# rekick2015-001.net
KiCad netlist of a schematic drawn in EAGLE
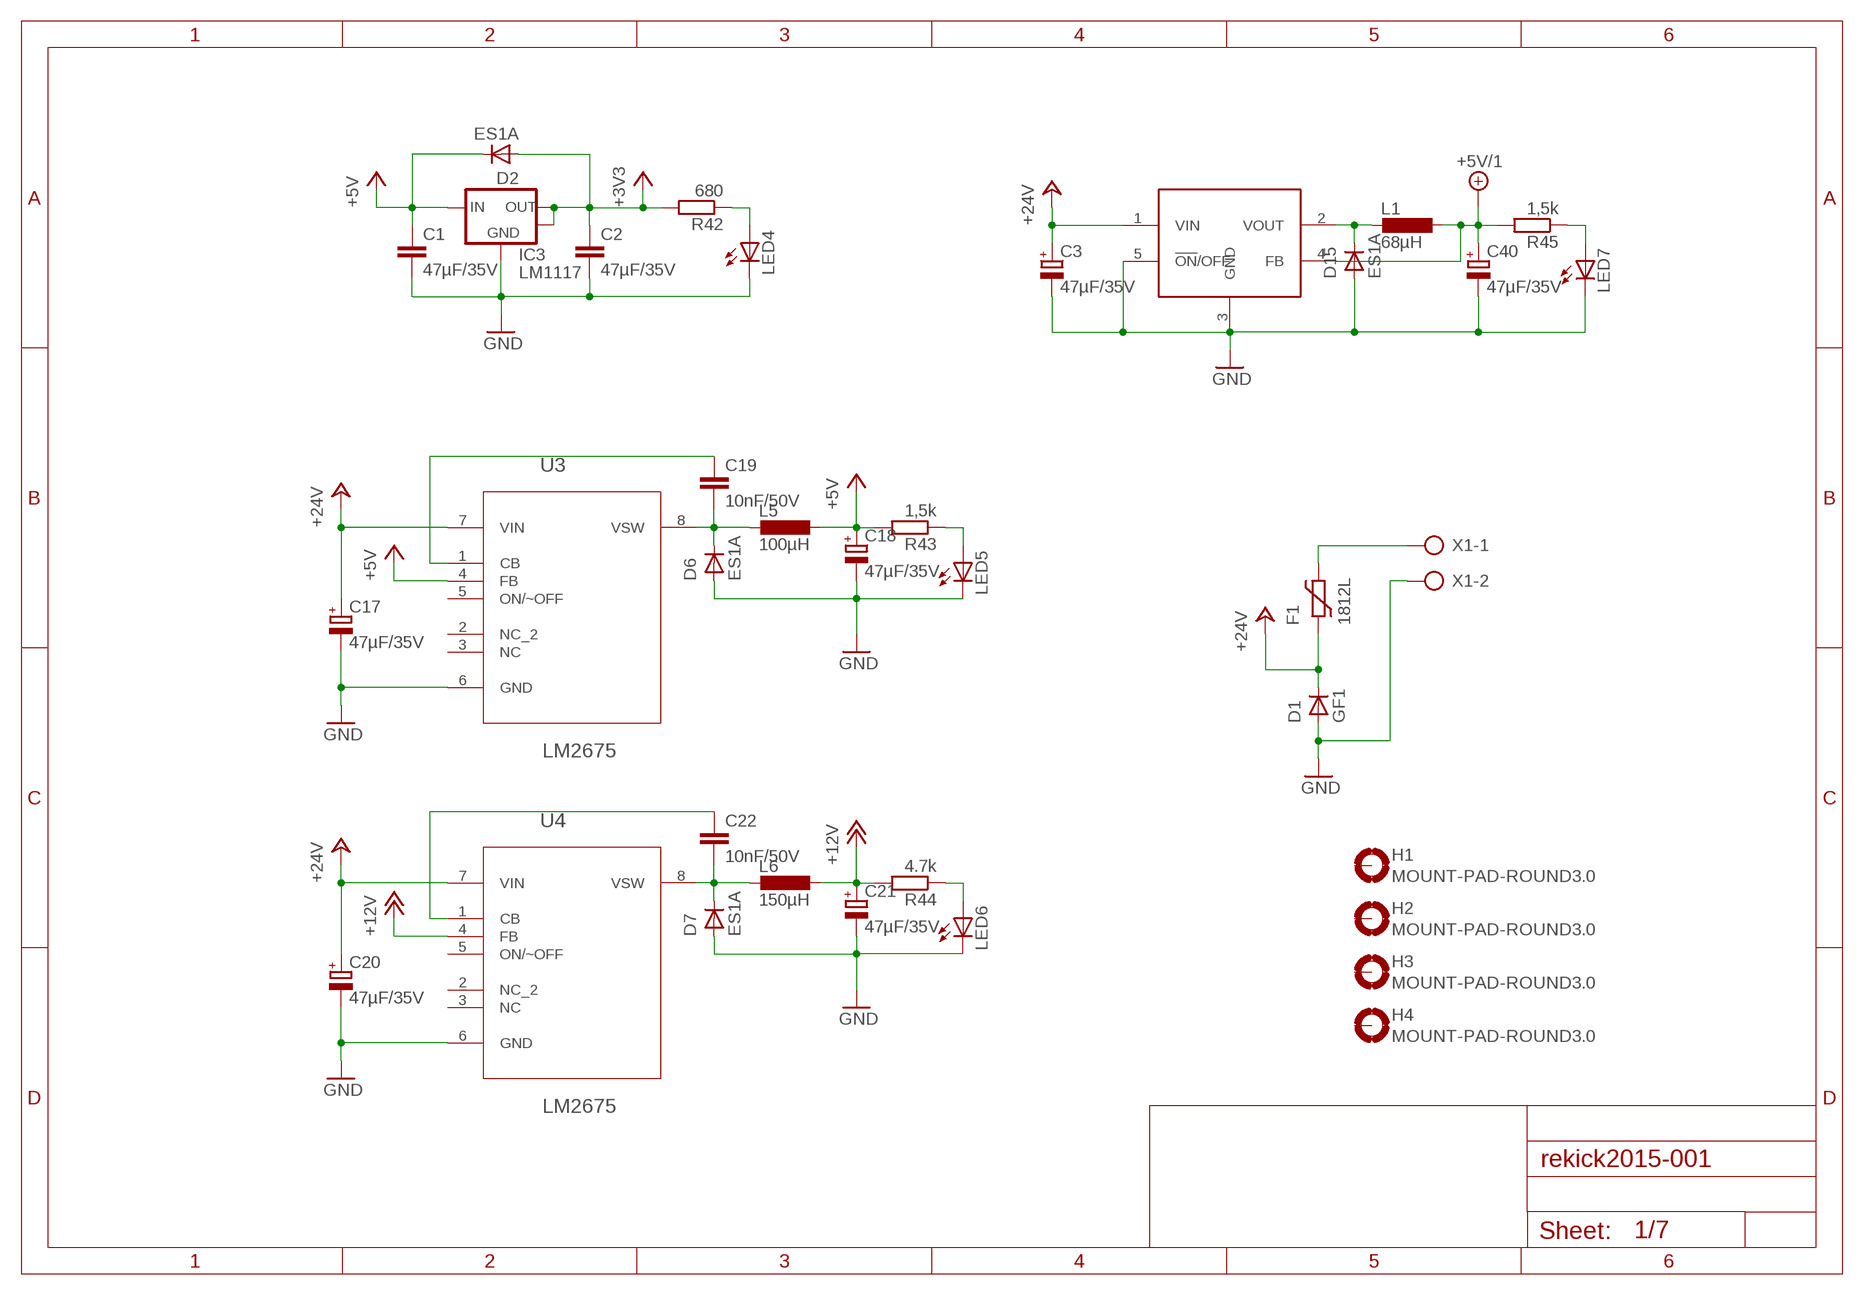
[diagram p0: schematic, sheet 1]
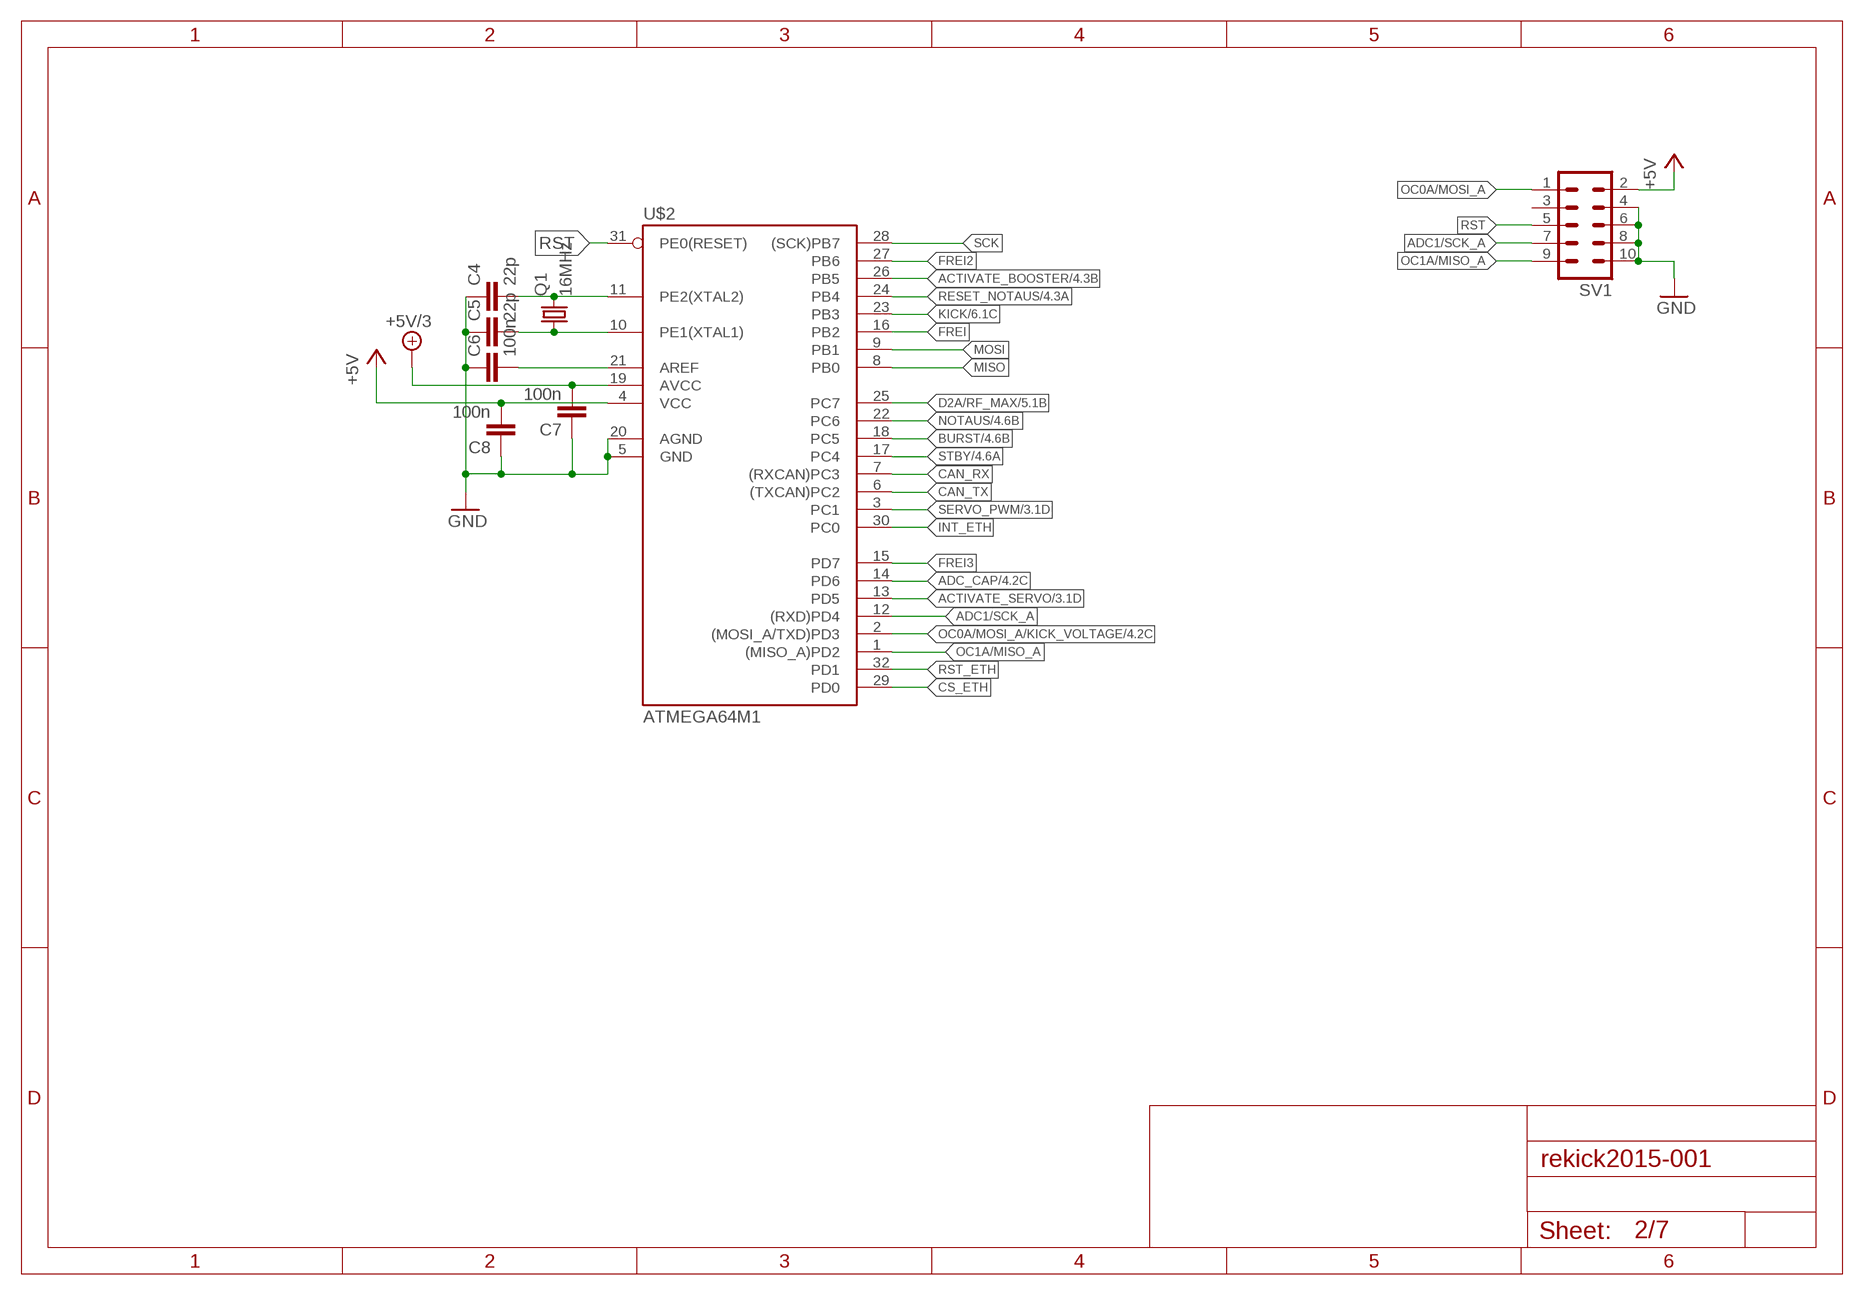
[diagram p1: schematic, sheet 2]
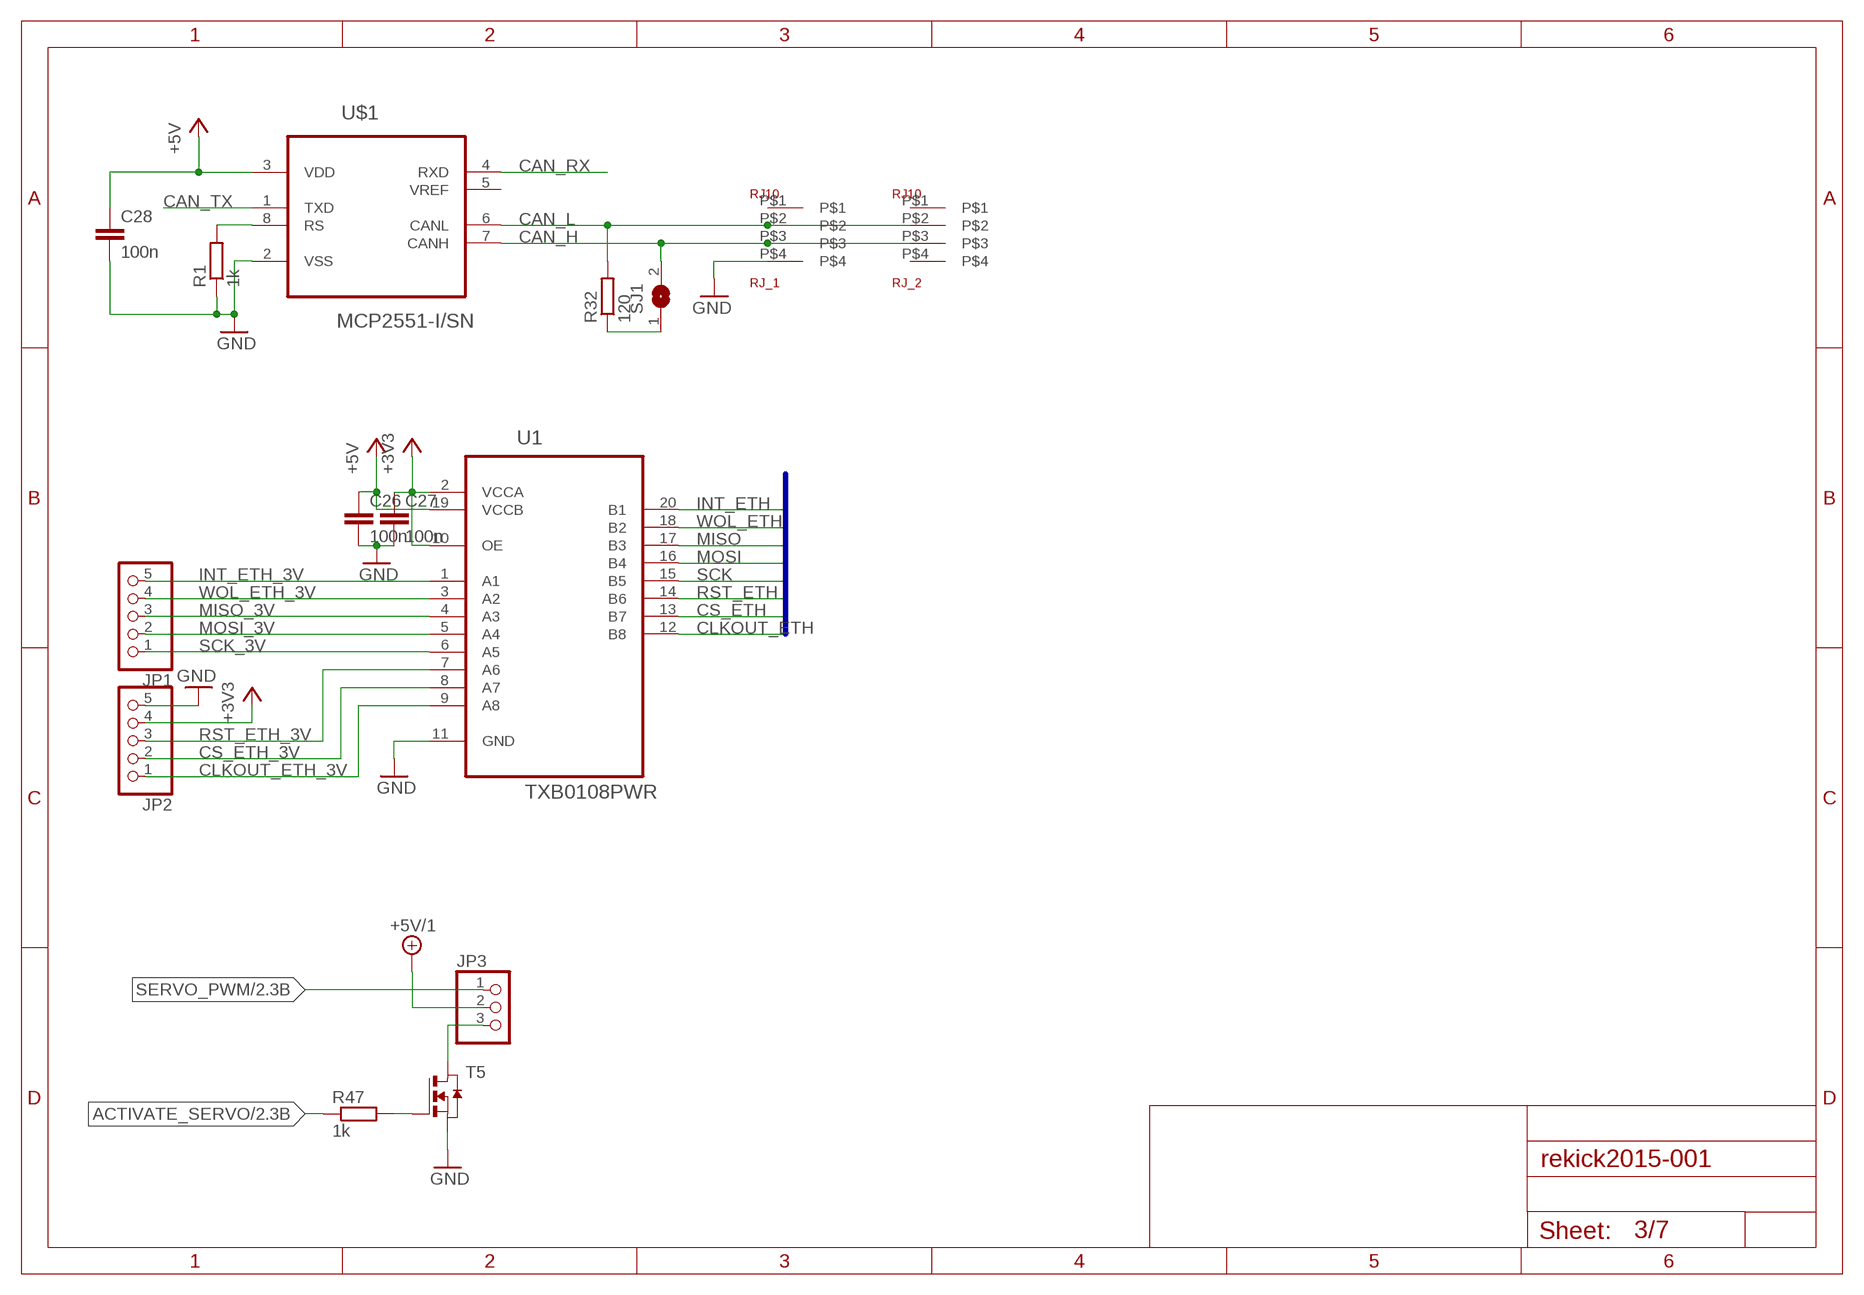
[diagram p2: schematic, sheet 3]
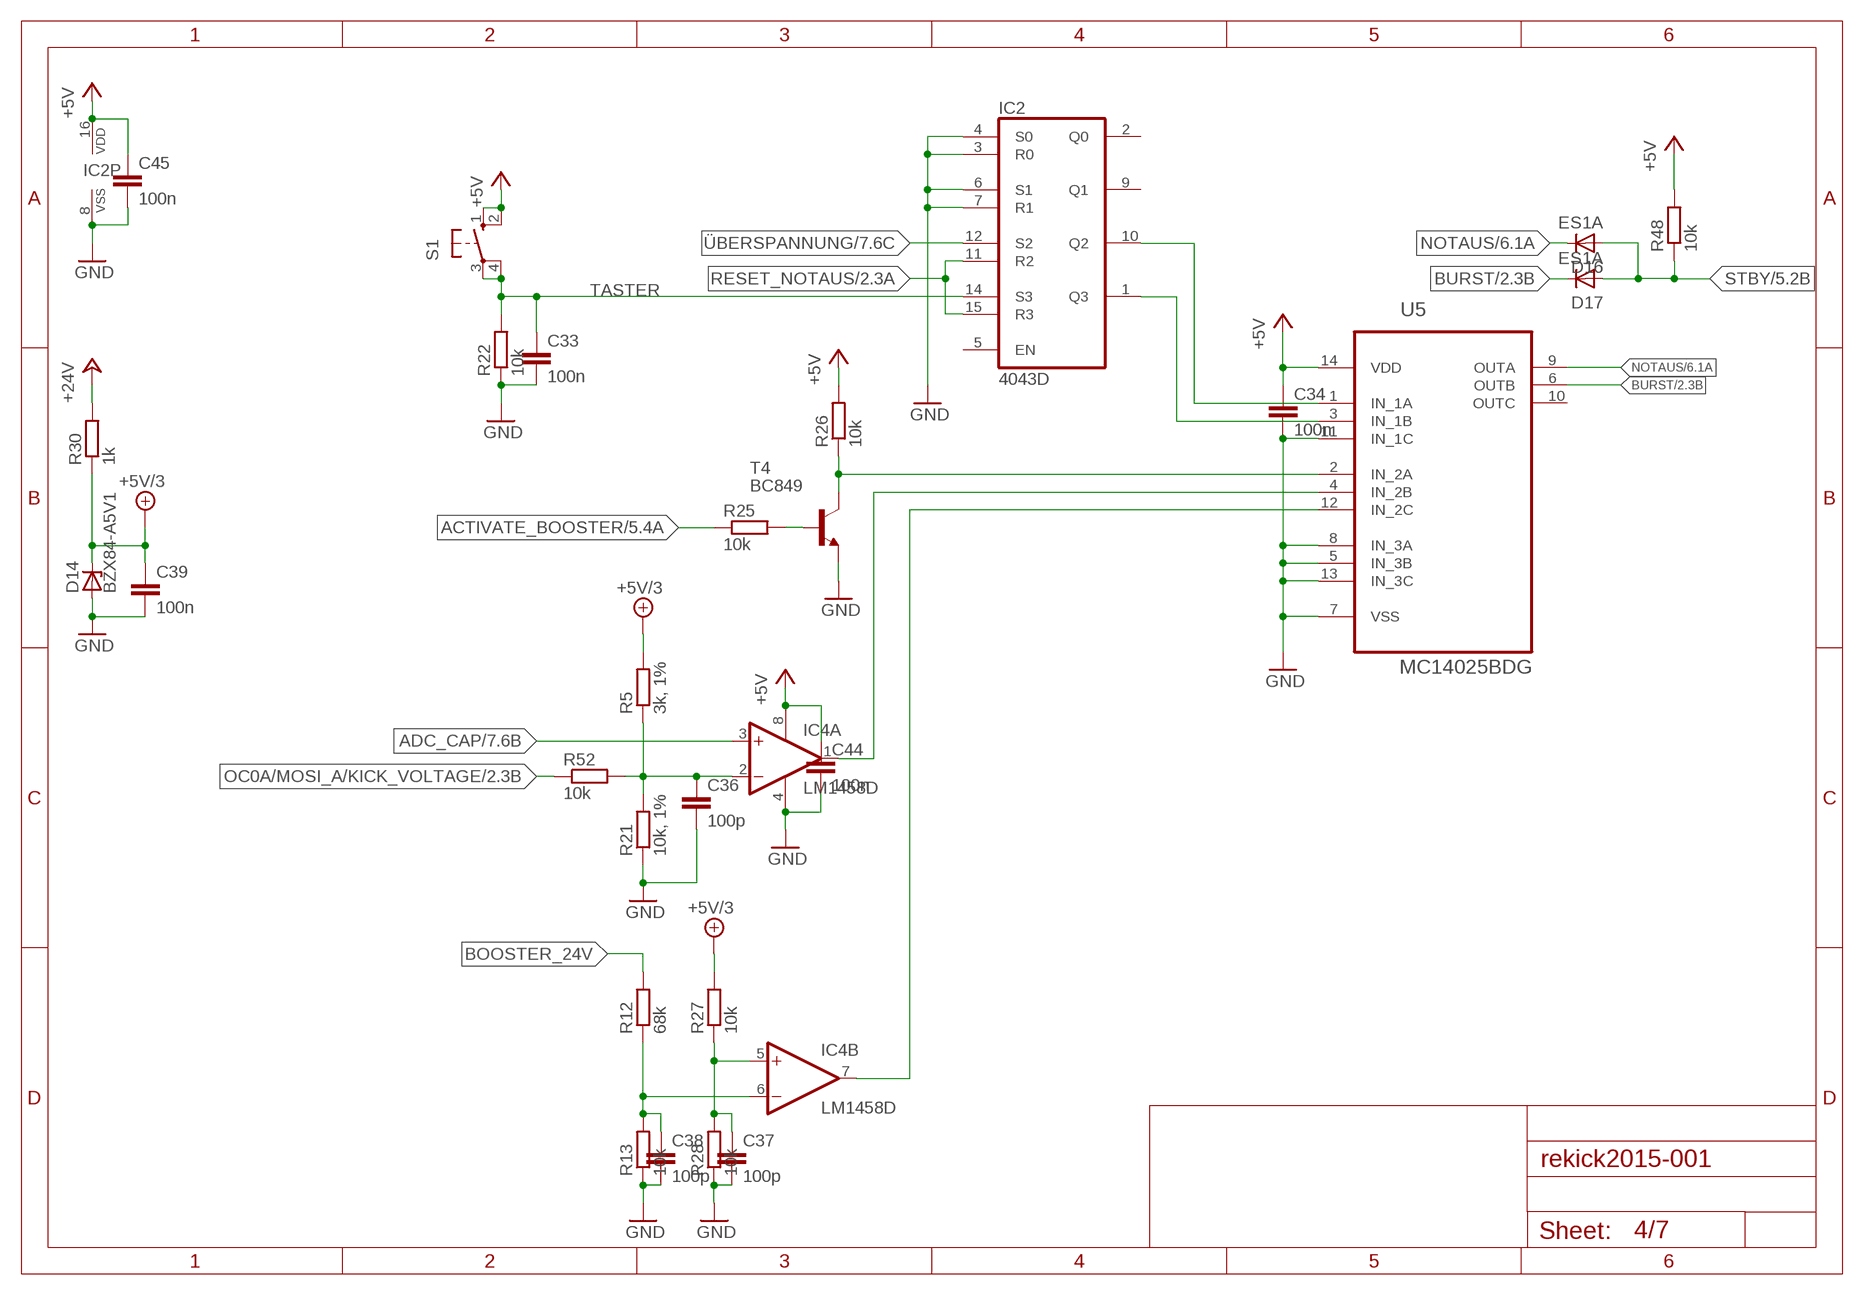
[diagram p3: schematic, sheet 4]
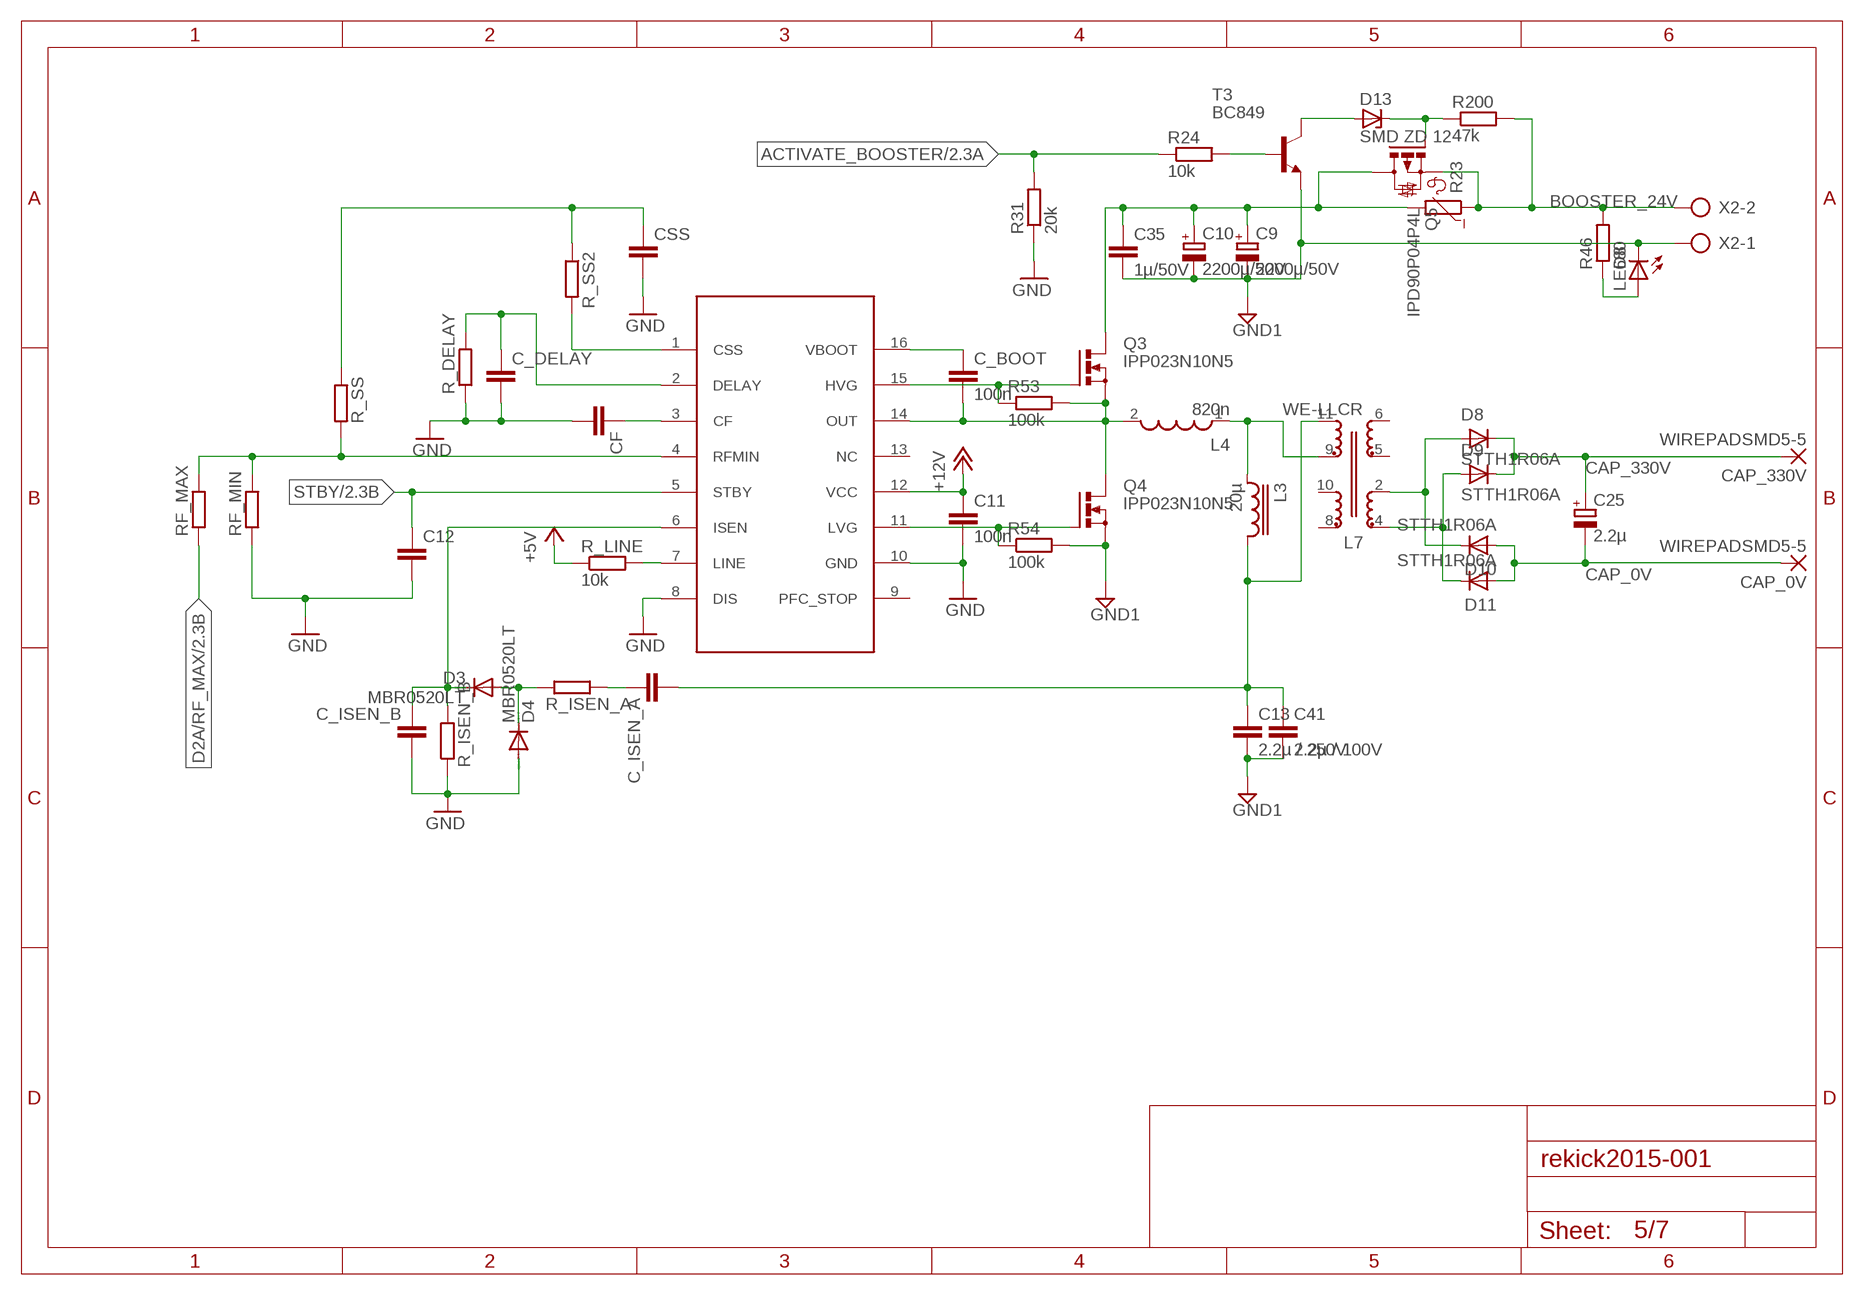
[diagram p4: schematic, sheet 5]
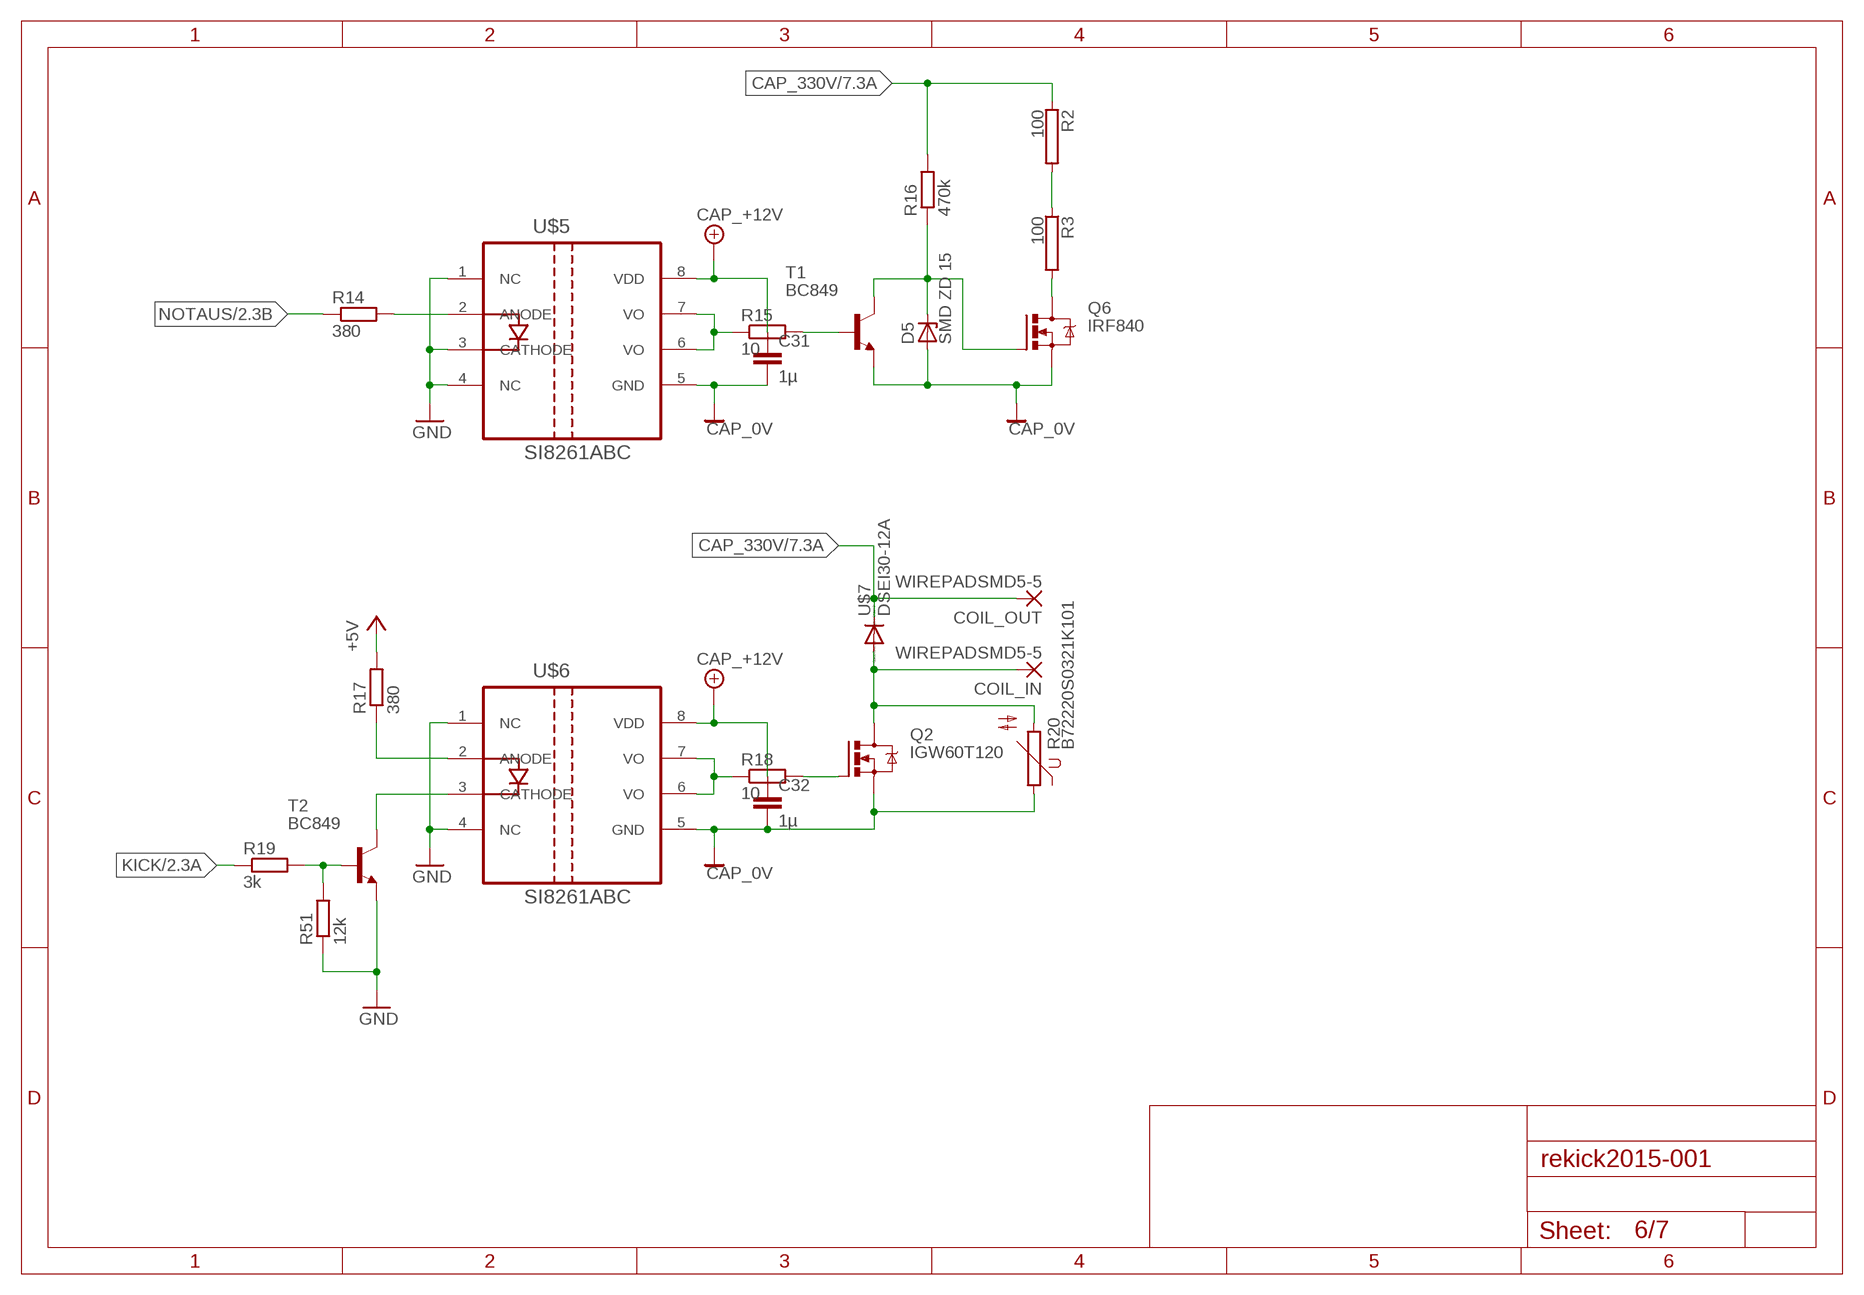
[diagram p5: schematic, sheet 6]
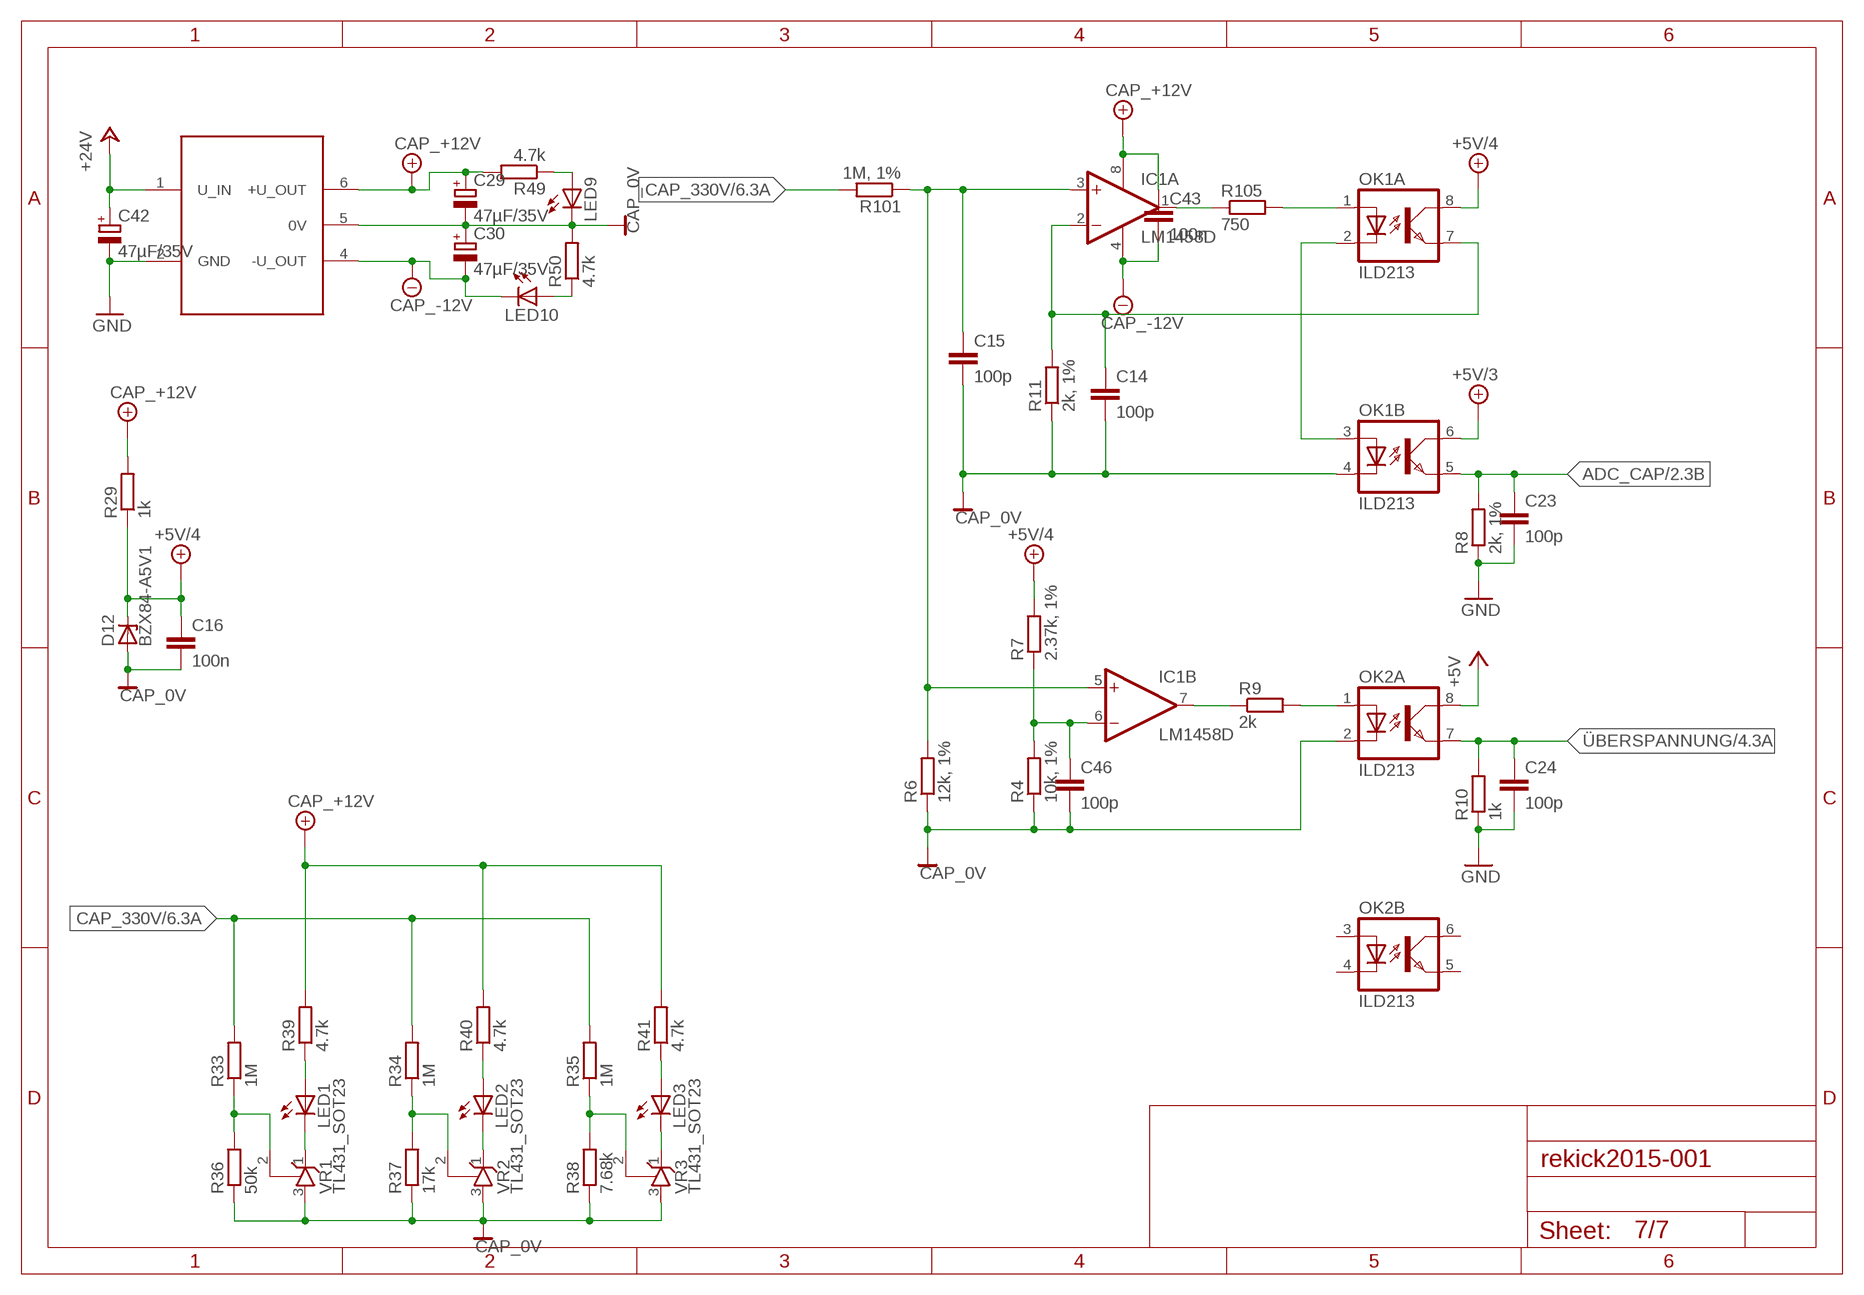
[diagram p6: schematic, sheet 7]

(export (version "E")
  (design (tool "Eeschema 10.0.6"))
  (components
    (comp (ref "C9")
      (value "2200µ/50V")
      (footprint "eagle-import:E5-13")
      (libsource (lib "eagle-import") (part "CPOL-EUE5-13"))
    )
    (comp (ref "C10")
      (value "2200µ/50V")
      (footprint "eagle-import:E5-13")
      (libsource (lib "eagle-import") (part "CPOL-EUE5-13"))
    )
    (comp (ref "C11")
      (value "100n")
      (footprint "eagle-import:C0603")
      (libsource (lib "eagle-import") (part "C-EUC0603"))
    )
    (comp (ref "C12")
      (value "C-EUC0603")
      (footprint "eagle-import:C0603")
      (libsource (lib "eagle-import") (part "C-EUC0603"))
    )
    (comp (ref "C13")
      (value "2.2µ / 250V")
      (footprint "eagle-import:C2220K")
      (libsource (lib "eagle-import") (part "C-EUC2220K"))
    )
    (comp (ref "C25")
      (value "2.2µ")
      (footprint "eagle-import:E5-10,5")
      (libsource (lib "eagle-import") (part "CPOL-EUE5-10.5"))
    )
    (comp (ref "C35")
      (value "1µ/50V")
      (footprint "eagle-import:C0603")
      (libsource (lib "eagle-import") (part "C-EUC0603"))
    )
    (comp (ref "C41")
      (value "2.2µ / 100V")
      (footprint "eagle-import:C1210K")
      (libsource (lib "eagle-import") (part "C-EUC1210K"))
    )
    (comp (ref "CAP_0V")
      (value "WIREPADSMD5-5")
      (footprint "eagle-import:5-5")
      (libsource (lib "eagle-import") (part "WIREPADSMD5-5"))
    )
    (comp (ref "CAP_330V")
      (value "WIREPADSMD5-5")
      (footprint "eagle-import:5-5")
      (libsource (lib "eagle-import") (part "WIREPADSMD5-5"))
    )
    (comp (ref "CF")
      (value "C-EUC0603")
      (footprint "eagle-import:C0603")
      (libsource (lib "eagle-import") (part "C-EUC0603"))
    )
    (comp (ref "CSS")
      (value "C-EUC0603")
      (footprint "eagle-import:C0603")
      (libsource (lib "eagle-import") (part "C-EUC0603"))
    )
    (comp (ref "C_BOOT")
      (value "100n")
      (footprint "eagle-import:C0603")
      (libsource (lib "eagle-import") (part "C-EUC0603"))
    )
    (comp (ref "C_DELAY")
      (value "C-EUC0603")
      (footprint "eagle-import:C0603")
      (libsource (lib "eagle-import") (part "C-EUC0603"))
    )
    (comp (ref "C_ISEN_A")
      (value "C-EUC0603")
      (footprint "eagle-import:C0603")
      (libsource (lib "eagle-import") (part "C-EUC0603"))
    )
    (comp (ref "C_ISEN_B")
      (value "C-EUC0603")
      (footprint "eagle-import:C0603")
      (libsource (lib "eagle-import") (part "C-EUC0603"))
    )
    (comp (ref "D3")
      (value "MBR0520LT")
      (footprint "eagle-import:SOD123")
      (libsource (lib "eagle-import") (part "MBR0520LT"))
    )
    (comp (ref "D4")
      (value "MBR0520LT")
      (footprint "eagle-import:SOD123")
      (libsource (lib "eagle-import") (part "MBR0520LT"))
    )
    (comp (ref "D8")
      (value "STTH1R06A")
      (footprint "eagle-import:SMA-DO214AC")
      (libsource (lib "eagle-import") (part "GF1"))
    )
    (comp (ref "D9")
      (value "STTH1R06A")
      (footprint "eagle-import:SMA-DO214AC")
      (libsource (lib "eagle-import") (part "GF1"))
    )
    (comp (ref "D10")
      (value "STTH1R06A")
      (footprint "eagle-import:SMA-DO214AC")
      (libsource (lib "eagle-import") (part "GF1"))
    )
    (comp (ref "D11")
      (value "STTH1R06A")
      (footprint "eagle-import:SMA-DO214AC")
      (libsource (lib "eagle-import") (part "GF1"))
    )
    (comp (ref "D13")
      (value "SMD ZD 12")
      (footprint "eagle-import:TO236")
      (libsource (lib "eagle-import") (part "BZX84CSMD"))
    )
    (comp (ref "L3")
      (value "20µ")
      (footprint "eagle-import:SRR1210")
      (libsource (lib "eagle-import") (part "SRR1210"))
    )
    (comp (ref "L4")
      (value "820n")
      (footprint "eagle-import:WE-HCI_1890")
      (libsource (lib "eagle-import") (part "WE-HCI_1890"))
    )
    (comp (ref "L7")
      (value "WE-LLCR")
      (footprint "eagle-import:WE-LLCR_ETD34")
      (libsource (lib "eagle-import") (part "WE-LLCR_ETD34"))
    )
    (comp (ref "LED8")
      (value "LEDCHIP-LED0805")
      (footprint "eagle-import:CHIP-LED0805")
      (libsource (lib "eagle-import") (part "LEDCHIP-LED0805"))
    )
    (comp (ref "Q3")
      (value "IPP023N10N5")
      (footprint "eagle-import:TO220BV")
      (libsource (lib "eagle-import") (part "PMOSFET_NTO220BV"))
    )
    (comp (ref "Q4")
      (value "IPP023N10N5")
      (footprint "eagle-import:TO220BV")
      (libsource (lib "eagle-import") (part "PMOSFET_NTO220BV"))
    )
    (comp (ref "Q5")
      (value "IPD90P04P4L")
      (footprint "eagle-import:D-PAK_TO252AA")
      (libsource (lib "eagle-import") (part "IRF?5305R"))
    )
    (comp (ref "R23")
      (value "NTC644A")
      (footprint "eagle-import:N644A")
      (libsource (lib "eagle-import") (part "NTC644A"))
    )
    (comp (ref "R24")
      (value "10k")
      (footprint "eagle-import:R0805")
      (libsource (lib "eagle-import") (part "R-EU_R0805"))
    )
    (comp (ref "R31")
      (value "20k")
      (footprint "eagle-import:R0805")
      (libsource (lib "eagle-import") (part "R-EU_R0805"))
    )
    (comp (ref "R46")
      (value "680")
      (footprint "eagle-import:R0805")
      (libsource (lib "eagle-import") (part "R-EU_R0805"))
    )
    (comp (ref "R53")
      (value "100k")
      (footprint "eagle-import:R0805")
      (libsource (lib "eagle-import") (part "R-EU_R0805"))
    )
    (comp (ref "R54")
      (value "100k")
      (footprint "eagle-import:R0805")
      (libsource (lib "eagle-import") (part "R-EU_R0805"))
    )
    (comp (ref "R200")
      (value "47k")
      (footprint "eagle-import:R0805")
      (libsource (lib "eagle-import") (part "R-EU_R0805"))
    )
    (comp (ref "RF_MAX")
      (value "R-EU_R0805")
      (footprint "eagle-import:R0805")
      (libsource (lib "eagle-import") (part "R-EU_R0805"))
    )
    (comp (ref "RF_MIN")
      (value "R-EU_R0805")
      (footprint "eagle-import:R0805")
      (libsource (lib "eagle-import") (part "R-EU_R0805"))
    )
    (comp (ref "R_DELAY")
      (value "R-EU_R0805")
      (footprint "eagle-import:R0805")
      (libsource (lib "eagle-import") (part "R-EU_R0805"))
    )
    (comp (ref "R_ISEN_A")
      (value "R-EU_R0805")
      (footprint "eagle-import:R0805")
      (libsource (lib "eagle-import") (part "R-EU_R0805"))
    )
    (comp (ref "R_ISEN_B")
      (value "R-EU_R0805")
      (footprint "eagle-import:R0805")
      (libsource (lib "eagle-import") (part "R-EU_R0805"))
    )
    (comp (ref "R_LINE")
      (value "10k")
      (footprint "eagle-import:R0805")
      (libsource (lib "eagle-import") (part "R-EU_R0805"))
    )
    (comp (ref "R_SS")
      (value "R-EU_R0805")
      (footprint "eagle-import:R0805")
      (libsource (lib "eagle-import") (part "R-EU_R0805"))
    )
    (comp (ref "R_SS2")
      (value "R-EU_R0805")
      (footprint "eagle-import:R0805")
      (libsource (lib "eagle-import") (part "R-EU_R0805"))
    )
    (comp (ref "T3")
      (value "BC849")
      (footprint "eagle-import:SOT23")
      (libsource (lib "eagle-import") (part "BC849"))
    )
    (comp (ref "U$3")
      (value "L6599")
      (footprint "eagle-import:SO16")
      (libsource (lib "eagle-import") (part "L6599"))
    )
    (comp (ref "X2")
      (value "AK500/2-H")
      (footprint "eagle-import:AK500_2-H")
      (libsource (lib "eagle-import") (part "AK500/2-H"))
    )
    (comp (ref "C14")
      (value "100p")
      (footprint "eagle-import:C0603")
      (libsource (lib "eagle-import") (part "C-EUC0603"))
    )
    (comp (ref "C15")
      (value "100p")
      (footprint "eagle-import:C0603")
      (libsource (lib "eagle-import") (part "C-EUC0603"))
    )
    (comp (ref "C16")
      (value "100n")
      (footprint "eagle-import:C0603")
      (libsource (lib "eagle-import") (part "C-EUC0603"))
    )
    (comp (ref "C23")
      (value "100p")
      (footprint "eagle-import:C0603")
      (libsource (lib "eagle-import") (part "C-EUC0603"))
    )
    (comp (ref "C24")
      (value "100p")
      (footprint "eagle-import:C0603")
      (libsource (lib "eagle-import") (part "C-EUC0603"))
    )
    (comp (ref "C29")
      (value "47µF/35V")
      (footprint "eagle-import:PANASONIC_D")
      (libsource (lib "eagle-import") (part "CPOL-EUD"))
    )
    (comp (ref "C30")
      (value "47µF/35V")
      (footprint "eagle-import:PANASONIC_D")
      (libsource (lib "eagle-import") (part "CPOL-EUD"))
    )
    (comp (ref "C42")
      (value "47µF/35V")
      (footprint "eagle-import:PANASONIC_D")
      (libsource (lib "eagle-import") (part "CPOL-EUD"))
    )
    (comp (ref "C43")
      (value "100n")
      (footprint "eagle-import:C0603")
      (libsource (lib "eagle-import") (part "C-EUC0603"))
    )
    (comp (ref "C46")
      (value "100p")
      (footprint "eagle-import:C0603")
      (libsource (lib "eagle-import") (part "C-EUC0603"))
    )
    (comp (ref "D12")
      (value "BZX84-A5V1")
      (footprint "eagle-import:TO236")
      (libsource (lib "eagle-import") (part "BZX84CSMD"))
    )
    (comp (ref "IC1")
      (value "LM1458D")
      (footprint "eagle-import:SO08")
      (libsource (lib "eagle-import") (part "1458DLM"))
    )
    (comp (ref "LED1")
      (value "LEDCHIP-LED0805")
      (footprint "eagle-import:CHIP-LED0805")
      (libsource (lib "eagle-import") (part "LEDCHIP-LED0805"))
    )
    (comp (ref "LED2")
      (value "LEDCHIP-LED0805")
      (footprint "eagle-import:CHIP-LED0805")
      (libsource (lib "eagle-import") (part "LEDCHIP-LED0805"))
    )
    (comp (ref "LED3")
      (value "LEDCHIP-LED0805")
      (footprint "eagle-import:CHIP-LED0805")
      (libsource (lib "eagle-import") (part "LEDCHIP-LED0805"))
    )
    (comp (ref "LED9")
      (value "LEDCHIP-LED0805")
      (footprint "eagle-import:CHIP-LED0805")
      (libsource (lib "eagle-import") (part "LEDCHIP-LED0805"))
    )
    (comp (ref "LED10")
      (value "LEDCHIP-LED0805")
      (footprint "eagle-import:CHIP-LED0805")
      (libsource (lib "eagle-import") (part "LEDCHIP-LED0805"))
    )
    (comp (ref "OK1")
      (value "ILD213")
      (footprint "eagle-import:SOIC08")
      (libsource (lib "eagle-import") (part "ILD213"))
    )
    (comp (ref "OK2")
      (value "ILD213")
      (footprint "eagle-import:SOIC08")
      (libsource (lib "eagle-import") (part "ILD213"))
    )
    (comp (ref "R4")
      (value "10k, 1%")
      (footprint "eagle-import:R0805")
      (libsource (lib "eagle-import") (part "R-EU_R0805"))
    )
    (comp (ref "R6")
      (value "12k, 1%")
      (footprint "eagle-import:R0805")
      (libsource (lib "eagle-import") (part "R-EU_R0805"))
    )
    (comp (ref "R7")
      (value "2.37k, 1%")
      (footprint "eagle-import:R0805")
      (libsource (lib "eagle-import") (part "R-EU_R0805"))
    )
    (comp (ref "R8")
      (value "2k, 1%")
      (footprint "eagle-import:R0805")
      (libsource (lib "eagle-import") (part "R-EU_R0805"))
    )
    (comp (ref "R9")
      (value "2k")
      (footprint "eagle-import:R0805")
      (libsource (lib "eagle-import") (part "R-EU_R0805"))
    )
    (comp (ref "R10")
      (value "1k")
      (footprint "eagle-import:R0805")
      (libsource (lib "eagle-import") (part "R-EU_R0805"))
    )
    (comp (ref "R11")
      (value "2k, 1%")
      (footprint "eagle-import:R0805")
      (libsource (lib "eagle-import") (part "R-EU_R0805"))
    )
    (comp (ref "R29")
      (value "1k")
      (footprint "eagle-import:R0805")
      (libsource (lib "eagle-import") (part "R-EU_R0805"))
    )
    (comp (ref "R33")
      (value "1M")
      (footprint "eagle-import:R2512")
      (libsource (lib "eagle-import") (part "R-EU_R2512"))
    )
    (comp (ref "R34")
      (value "1M")
      (footprint "eagle-import:R2512")
      (libsource (lib "eagle-import") (part "R-EU_R2512"))
    )
    (comp (ref "R35")
      (value "1M")
      (footprint "eagle-import:R2512")
      (libsource (lib "eagle-import") (part "R-EU_R2512"))
    )
    (comp (ref "R36")
      (value "50k")
      (footprint "eagle-import:R0805")
      (libsource (lib "eagle-import") (part "R-EU_R0805"))
    )
    (comp (ref "R37")
      (value "17k")
      (footprint "eagle-import:R0805")
      (libsource (lib "eagle-import") (part "R-EU_R0805"))
    )
    (comp (ref "R38")
      (value "7.68k")
      (footprint "eagle-import:R0805")
      (libsource (lib "eagle-import") (part "R-EU_R0805"))
    )
    (comp (ref "R39")
      (value "4.7k")
      (footprint "eagle-import:R0805")
      (libsource (lib "eagle-import") (part "R-EU_R0805"))
    )
    (comp (ref "R40")
      (value "4.7k")
      (footprint "eagle-import:R0805")
      (libsource (lib "eagle-import") (part "R-EU_R0805"))
    )
    (comp (ref "R41")
      (value "4.7k")
      (footprint "eagle-import:R0805")
      (libsource (lib "eagle-import") (part "R-EU_R0805"))
    )
    (comp (ref "R49")
      (value "4.7k")
      (footprint "eagle-import:R0805")
      (libsource (lib "eagle-import") (part "R-EU_R0805"))
    )
    (comp (ref "R50")
      (value "4.7k")
      (footprint "eagle-import:R0805")
      (libsource (lib "eagle-import") (part "R-EU_R0805"))
    )
    (comp (ref "R101")
      (value "1M, 1%")
      (footprint "eagle-import:R2512")
      (libsource (lib "eagle-import") (part "R-EU_R2512"))
    )
    (comp (ref "R105")
      (value "750")
      (footprint "eagle-import:R0805")
      (libsource (lib "eagle-import") (part "R-EU_R0805"))
    )
    (comp (ref "U$4")
      (value "TMH-D")
      (footprint "eagle-import:TMH-D")
      (libsource (lib "eagle-import") (part "TMH-D"))
    )
    (comp (ref "VR1")
      (value "TL431_SOT23")
      (footprint "eagle-import:SOT23")
      (libsource (lib "eagle-import") (part "TL431_SOT23"))
    )
    (comp (ref "VR2")
      (value "TL431_SOT23")
      (footprint "eagle-import:SOT23")
      (libsource (lib "eagle-import") (part "TL431_SOT23"))
    )
    (comp (ref "VR3")
      (value "TL431_SOT23")
      (footprint "eagle-import:SOT23")
      (libsource (lib "eagle-import") (part "TL431_SOT23"))
    )
    (comp (ref "C1")
      (value "47µF/35V")
      (footprint "eagle-import:C0603")
      (libsource (lib "eagle-import") (part "C-EUC0603"))
    )
    (comp (ref "C2")
      (value "47µF/35V")
      (footprint "eagle-import:C0603")
      (libsource (lib "eagle-import") (part "C-EUC0603"))
    )
    (comp (ref "C3")
      (value "47µF/35V")
      (footprint "eagle-import:PANASONIC_D")
      (libsource (lib "eagle-import") (part "CPOL-EUD"))
    )
    (comp (ref "C17")
      (value "47µF/35V")
      (footprint "eagle-import:PANASONIC_D")
      (libsource (lib "eagle-import") (part "CPOL-EUD"))
    )
    (comp (ref "C18")
      (value "47µF/35V")
      (footprint "eagle-import:PANASONIC_D")
      (libsource (lib "eagle-import") (part "CPOL-EUD"))
    )
    (comp (ref "C19")
      (value "10nF/50V")
      (footprint "eagle-import:C0603")
      (libsource (lib "eagle-import") (part "C-EUC0603"))
    )
    (comp (ref "C20")
      (value "47µF/35V")
      (footprint "eagle-import:PANASONIC_D")
      (libsource (lib "eagle-import") (part "CPOL-EUD"))
    )
    (comp (ref "C21")
      (value "47µF/35V")
      (footprint "eagle-import:PANASONIC_D")
      (libsource (lib "eagle-import") (part "CPOL-EUD"))
    )
    (comp (ref "C22")
      (value "10nF/50V")
      (footprint "eagle-import:C0603")
      (libsource (lib "eagle-import") (part "C-EUC0603"))
    )
    (comp (ref "C40")
      (value "47µF/35V")
      (footprint "eagle-import:PANASONIC_D")
      (libsource (lib "eagle-import") (part "CPOL-EUD"))
    )
    (comp (ref "D1")
      (value "GF1")
      (footprint "eagle-import:SMA-DO214AC")
      (libsource (lib "eagle-import") (part "GF1"))
    )
    (comp (ref "D2")
      (value "ES1A")
      (footprint "eagle-import:SMA-DO214AC")
      (libsource (lib "eagle-import") (part "GF1"))
    )
    (comp (ref "D6")
      (value "ES1A")
      (footprint "eagle-import:SMA-DO214AC")
      (libsource (lib "eagle-import") (part "GF1"))
    )
    (comp (ref "D7")
      (value "ES1A")
      (footprint "eagle-import:SMA-DO214AC")
      (libsource (lib "eagle-import") (part "GF1"))
    )
    (comp (ref "D15")
      (value "ES1A")
      (footprint "eagle-import:SMA-DO214AC")
      (libsource (lib "eagle-import") (part "GF1"))
    )
    (comp (ref "F1")
      (value "1812L")
      (footprint "eagle-import:1812L")
      (libsource (lib "eagle-import") (part "1812L"))
    )
    (comp (ref "H1")
      (value "MOUNT-PAD-ROUND3.0")
      (footprint "eagle-import:3,0-PAD")
      (libsource (lib "eagle-import") (part "MOUNT-PAD-ROUND3.0"))
    )
    (comp (ref "H2")
      (value "MOUNT-PAD-ROUND3.0")
      (footprint "eagle-import:3,0-PAD")
      (libsource (lib "eagle-import") (part "MOUNT-PAD-ROUND3.0"))
    )
    (comp (ref "H3")
      (value "MOUNT-PAD-ROUND3.0")
      (footprint "eagle-import:3,0-PAD")
      (libsource (lib "eagle-import") (part "MOUNT-PAD-ROUND3.0"))
    )
    (comp (ref "H4")
      (value "MOUNT-PAD-ROUND3.0")
      (footprint "eagle-import:3,0-PAD")
      (libsource (lib "eagle-import") (part "MOUNT-PAD-ROUND3.0"))
    )
    (comp (ref "IC3")
      (value "LM1117")
      (footprint "eagle-import:SOT223")
      (libsource (lib "eagle-import") (part "LM1117"))
    )
    (comp (ref "L1")
      (value "68µH")
      (footprint "eagle-import:PISM")
      (libsource (lib "eagle-import") (part "L-EUPISM"))
    )
    (comp (ref "L5")
      (value "100µH")
      (footprint "eagle-import:PISM")
      (libsource (lib "eagle-import") (part "L-EUPISM"))
    )
    (comp (ref "L6")
      (value "150µH")
      (footprint "eagle-import:PISM")
      (libsource (lib "eagle-import") (part "L-EUPISM"))
    )
    (comp (ref "LED4")
      (value "LEDCHIP-LED0805")
      (footprint "eagle-import:CHIP-LED0805")
      (libsource (lib "eagle-import") (part "LEDCHIP-LED0805"))
    )
    (comp (ref "LED5")
      (value "LEDCHIP-LED0805")
      (footprint "eagle-import:CHIP-LED0805")
      (libsource (lib "eagle-import") (part "LEDCHIP-LED0805"))
    )
    (comp (ref "LED6")
      (value "LEDCHIP-LED0805")
      (footprint "eagle-import:CHIP-LED0805")
      (libsource (lib "eagle-import") (part "LEDCHIP-LED0805"))
    )
    (comp (ref "LED7")
      (value "LEDCHIP-LED0805")
      (footprint "eagle-import:CHIP-LED0805")
      (libsource (lib "eagle-import") (part "LEDCHIP-LED0805"))
    )
    (comp (ref "R42")
      (value "680")
      (footprint "eagle-import:R0805")
      (libsource (lib "eagle-import") (part "R-EU_R0805"))
    )
    (comp (ref "R43")
      (value "1,5k")
      (footprint "eagle-import:R0805")
      (libsource (lib "eagle-import") (part "R-EU_R0805"))
    )
    (comp (ref "R44")
      (value "4.7k")
      (footprint "eagle-import:R0805")
      (libsource (lib "eagle-import") (part "R-EU_R0805"))
    )
    (comp (ref "R45")
      (value "1,5k")
      (footprint "eagle-import:R0805")
      (libsource (lib "eagle-import") (part "R-EU_R0805"))
    )
    (comp (ref "U$8")
      (value "LM2576")
      (footprint "eagle-import:TO220511")
      (libsource (lib "eagle-import") (part "LM2576"))
    )
    (comp (ref "U3")
      (value "LM2675")
      (footprint "eagle-import:SOIC127P620X175-8N")
      (fields (field (name "MPN") "LM2675M-3.3"))
      (libsource (lib "eagle-import") (part "LM2675M-3.3"))
    )
    (comp (ref "U4")
      (value "LM2675")
      (footprint "eagle-import:SOIC127P620X175-8N")
      (fields (field (name "MPN") "LM2675M-3.3"))
      (libsource (lib "eagle-import") (part "LM2675M-3.3"))
    )
    (comp (ref "X1")
      (value "AK500/2-H")
      (footprint "eagle-import:AK500_2-H")
      (libsource (lib "eagle-import") (part "AK500/2-H"))
    )
    (comp (ref "C33")
      (value "100n")
      (footprint "eagle-import:C0603")
      (libsource (lib "eagle-import") (part "C-EUC0603"))
    )
    (comp (ref "C34")
      (value "100n")
      (footprint "eagle-import:C0603")
      (libsource (lib "eagle-import") (part "C-EUC0603"))
    )
    (comp (ref "C36")
      (value "100p")
      (footprint "eagle-import:C0603")
      (libsource (lib "eagle-import") (part "C-EUC0603"))
    )
    (comp (ref "C37")
      (value "100p")
      (footprint "eagle-import:C0603")
      (libsource (lib "eagle-import") (part "C-EUC0603"))
    )
    (comp (ref "C38")
      (value "100p")
      (footprint "eagle-import:C0603")
      (libsource (lib "eagle-import") (part "C-EUC0603"))
    )
    (comp (ref "C39")
      (value "100n")
      (footprint "eagle-import:C0603")
      (libsource (lib "eagle-import") (part "C-EUC0603"))
    )
    (comp (ref "C44")
      (value "100n")
      (footprint "eagle-import:C0603")
      (libsource (lib "eagle-import") (part "C-EUC0603"))
    )
    (comp (ref "C45")
      (value "100n")
      (footprint "eagle-import:C0603")
      (libsource (lib "eagle-import") (part "C-EUC0603"))
    )
    (comp (ref "D14")
      (value "BZX84-A5V1")
      (footprint "eagle-import:TO236")
      (libsource (lib "eagle-import") (part "BZX84CSMD"))
    )
    (comp (ref "D16")
      (value "ES1A")
      (footprint "eagle-import:SMA-DO214AC")
      (libsource (lib "eagle-import") (part "GF1"))
    )
    (comp (ref "D17")
      (value "ES1A")
      (footprint "eagle-import:SMA-DO214AC")
      (libsource (lib "eagle-import") (part "GF1"))
    )
    (comp (ref "IC2")
      (value "4043D")
      (footprint "eagle-import:SO16")
      (libsource (lib "eagle-import") (part "4043D"))
    )
    (comp (ref "IC4")
      (value "LM1458D")
      (footprint "eagle-import:SO08")
      (libsource (lib "eagle-import") (part "1458DLM"))
    )
    (comp (ref "R5")
      (value "3k, 1%")
      (footprint "eagle-import:R0805")
      (libsource (lib "eagle-import") (part "R-EU_R0805"))
    )
    (comp (ref "R12")
      (value "68k")
      (footprint "eagle-import:R0805")
      (libsource (lib "eagle-import") (part "R-EU_R0805"))
    )
    (comp (ref "R13")
      (value "10k")
      (footprint "eagle-import:R0805")
      (libsource (lib "eagle-import") (part "R-EU_R0805"))
    )
    (comp (ref "R21")
      (value "10k, 1%")
      (footprint "eagle-import:R0805")
      (libsource (lib "eagle-import") (part "R-EU_R0805"))
    )
    (comp (ref "R22")
      (value "10k")
      (footprint "eagle-import:R0805")
      (libsource (lib "eagle-import") (part "R-EU_R0805"))
    )
    (comp (ref "R25")
      (value "10k")
      (footprint "eagle-import:R0805")
      (libsource (lib "eagle-import") (part "R-EU_R0805"))
    )
    (comp (ref "R26")
      (value "10k")
      (footprint "eagle-import:R0805")
      (libsource (lib "eagle-import") (part "R-EU_R0805"))
    )
    (comp (ref "R27")
      (value "10k")
      (footprint "eagle-import:R0805")
      (libsource (lib "eagle-import") (part "R-EU_R0805"))
    )
    (comp (ref "R28")
      (value "10k")
      (footprint "eagle-import:R0805")
      (libsource (lib "eagle-import") (part "R-EU_R0805"))
    )
    (comp (ref "R30")
      (value "1k")
      (footprint "eagle-import:R0805")
      (libsource (lib "eagle-import") (part "R-EU_R0805"))
    )
    (comp (ref "R48")
      (value "10k")
      (footprint "eagle-import:R0805")
      (libsource (lib "eagle-import") (part "R-EU_R0805"))
    )
    (comp (ref "R52")
      (value "10k")
      (footprint "eagle-import:R0805")
      (libsource (lib "eagle-import") (part "R-EU_R0805"))
    )
    (comp (ref "S1")
      (value "10-XX")
      (footprint "eagle-import:B3F-10XX")
      (libsource (lib "eagle-import") (part "10-XX"))
    )
    (comp (ref "T4")
      (value "BC849")
      (footprint "eagle-import:SOT23")
      (libsource (lib "eagle-import") (part "BC849"))
    )
    (comp (ref "U5")
      (value "MC14025BDG")
      (footprint "eagle-import:SOIC127P600X175-14N")
      (libsource (lib "eagle-import") (part "MC14025BDG"))
    )
    (comp (ref "C26")
      (value "100n")
      (footprint "eagle-import:C0603")
      (libsource (lib "eagle-import") (part "C-EUC0603"))
    )
    (comp (ref "C27")
      (value "100n")
      (footprint "eagle-import:C0603")
      (libsource (lib "eagle-import") (part "C-EUC0603"))
    )
    (comp (ref "C28")
      (value "100n")
      (footprint "eagle-import:C0603")
      (libsource (lib "eagle-import") (part "C-EUC0603"))
    )
    (comp (ref "JP1")
      (value "PINHD-1X5")
      (footprint "eagle-import:1X05")
      (libsource (lib "eagle-import") (part "PINHD-1X5"))
    )
    (comp (ref "JP2")
      (value "PINHD-1X5")
      (footprint "eagle-import:1X05")
      (libsource (lib "eagle-import") (part "PINHD-1X5"))
    )
    (comp (ref "JP3")
      (value "PINHD-1X3")
      (footprint "eagle-import:1X03")
      (libsource (lib "eagle-import") (part "PINHD-1X3"))
    )
    (comp (ref "R1")
      (value "1k")
      (footprint "eagle-import:R0805")
      (libsource (lib "eagle-import") (part "R-EU_R0805"))
    )
    (comp (ref "R32")
      (value "120")
      (footprint "eagle-import:R0805")
      (libsource (lib "eagle-import") (part "R-EU_R0805"))
    )
    (comp (ref "R47")
      (value "1k")
      (footprint "eagle-import:R0805")
      (libsource (lib "eagle-import") (part "R-EU_R0805"))
    )
    (comp (ref "RJ_1")
      (value "RJ10")
      (footprint "eagle-import:RJ10")
      (libsource (lib "eagle-import") (part "RJ10"))
    )
    (comp (ref "RJ_2")
      (value "RJ10")
      (footprint "eagle-import:RJ10")
      (libsource (lib "eagle-import") (part "RJ10"))
    )
    (comp (ref "SJ1") (value "SJ") (footprint "eagle-import:SJ") (libsource (lib "eagle-import") (part "SJ")))
    (comp (ref "T5")
      (value "NMOSSOT23")
      (footprint "eagle-import:SOT-23")
      (libsource (lib "eagle-import") (part "NMOSSOT23"))
    )
    (comp (ref "U$1")
      (value "MCP2551-I/SN")
      (footprint "eagle-import:SOIC127P600X175-8N")
      (libsource (lib "eagle-import") (part "MCP2551-I/SN"))
    )
    (comp (ref "U1")
      (value "TXB0108PWR")
      (footprint "eagle-import:SOP65P640X120-20N")
      (libsource (lib "eagle-import") (part "TXB0108PWR"))
    )
    (comp (ref "C4")
      (value "22p")
      (footprint "eagle-import:C0603")
      (libsource (lib "eagle-import") (part "C-EUC0603"))
    )
    (comp (ref "C5")
      (value "22p")
      (footprint "eagle-import:C0603")
      (libsource (lib "eagle-import") (part "C-EUC0603"))
    )
    (comp (ref "C6")
      (value "100n")
      (footprint "eagle-import:C0603")
      (libsource (lib "eagle-import") (part "C-EUC0603"))
    )
    (comp (ref "C7")
      (value "100n")
      (footprint "eagle-import:C0603")
      (libsource (lib "eagle-import") (part "C-EUC0603"))
    )
    (comp (ref "C8")
      (value "100n")
      (footprint "eagle-import:C0603")
      (libsource (lib "eagle-import") (part "C-EUC0603"))
    )
    (comp (ref "Q1")
      (value "16MHz")
      (footprint "eagle-import:HC49UP")
      (libsource (lib "eagle-import") (part "CRYSTALHC49UP"))
    )
    (comp (ref "SV1")
      (value "ML10")
      (footprint "eagle-import:ML10")
      (libsource (lib "eagle-import") (part "ML10"))
    )
    (comp (ref "U$2")
      (value "ATMEGA64M1")
      (footprint "eagle-import:TQFP32-08")
      (libsource (lib "eagle-import") (part "ATMEGA64M1"))
    )
    (comp (ref "C31")
      (value "1µ")
      (footprint "eagle-import:C0603")
      (libsource (lib "eagle-import") (part "C-EUC0603"))
    )
    (comp (ref "C32")
      (value "1µ")
      (footprint "eagle-import:C0603")
      (libsource (lib "eagle-import") (part "C-EUC0603"))
    )
    (comp (ref "COIL_IN")
      (value "WIREPADSMD5-5")
      (footprint "eagle-import:5-5")
      (libsource (lib "eagle-import") (part "WIREPADSMD5-5"))
    )
    (comp (ref "COIL_OUT")
      (value "WIREPADSMD5-5")
      (footprint "eagle-import:5-5")
      (libsource (lib "eagle-import") (part "WIREPADSMD5-5"))
    )
    (comp (ref "D5")
      (value "SMD ZD 15")
      (footprint "eagle-import:TO236")
      (libsource (lib "eagle-import") (part "BZX84CSMD"))
    )
    (comp (ref "Q2")
      (value "IGW60T120")
      (footprint "eagle-import:TO247BV")
      (libsource (lib "eagle-import") (part "IRFPC40"))
    )
    (comp (ref "Q6")
      (value "IRF840")
      (footprint "eagle-import:TO220BV")
      (libsource (lib "eagle-import") (part "IRF740"))
    )
    (comp (ref "R2")
      (value "100")
      (footprint "eagle-import:HS25")
      (libsource (lib "eagle-import") (part "RHS25"))
    )
    (comp (ref "R3")
      (value "100")
      (footprint "eagle-import:HS25")
      (libsource (lib "eagle-import") (part "RHS25"))
    )
    (comp (ref "R14")
      (value "380")
      (footprint "eagle-import:R0805")
      (libsource (lib "eagle-import") (part "R-EU_R0805"))
    )
    (comp (ref "R15")
      (value "10")
      (footprint "eagle-import:R0805")
      (libsource (lib "eagle-import") (part "R-EU_R0805"))
    )
    (comp (ref "R16")
      (value "470k")
      (footprint "eagle-import:0207_15")
      (libsource (lib "eagle-import") (part "R-EU_0207/15"))
    )
    (comp (ref "R17")
      (value "380")
      (footprint "eagle-import:R0805")
      (libsource (lib "eagle-import") (part "R-EU_R0805"))
    )
    (comp (ref "R18")
      (value "10")
      (footprint "eagle-import:R0805")
      (libsource (lib "eagle-import") (part "R-EU_R0805"))
    )
    (comp (ref "R19")
      (value "3k")
      (footprint "eagle-import:R0805")
      (libsource (lib "eagle-import") (part "R-EU_R0805"))
    )
    (comp (ref "R20")
      (value "B72220S0321K101")
      (footprint "eagle-import:S20K320")
      (libsource (lib "eagle-import") (part "S20K320"))
    )
    (comp (ref "R51")
      (value "12k")
      (footprint "eagle-import:R0805")
      (libsource (lib "eagle-import") (part "R-EU_R0805"))
    )
    (comp (ref "T1")
      (value "BC849")
      (footprint "eagle-import:SOT23")
      (libsource (lib "eagle-import") (part "BC849"))
    )
    (comp (ref "T2")
      (value "BC849")
      (footprint "eagle-import:SOT23")
      (libsource (lib "eagle-import") (part "BC849"))
    )
    (comp (ref "U$5")
      (value "SI8261ABC")
      (footprint "eagle-import:SOIC-8")
      (libsource (lib "eagle-import") (part "SI8261ABC"))
    )
    (comp (ref "U$6")
      (value "SI8261ABC")
      (footprint "eagle-import:SOIC-8")
      (libsource (lib "eagle-import") (part "SI8261ABC"))
    )
    (comp (ref "U$7")
      (value "DSEI30-12A")
      (footprint "eagle-import:TO247AD")
      (libsource (lib "eagle-import") (part "DSEI30-12A"))
    )
  )
  (nets
    (net (code "1") (name "+3V3") (class "Default")
      (node (ref "C2") (pin "1") (pinfunction "1_1") (pintype "passive"))
      (node (ref "C27") (pin "1") (pinfunction "1_1") (pintype "passive"))
      (node (ref "D2") (pin "A") (pinfunction "A_A") (pintype "passive"))
      (node (ref "IC3") (pin "2") (pinfunction "OUT_2") (pintype "passive"))
      (node (ref "IC3") (pin "4") (pinfunction "OUT_4") (pintype "input"))
      (node (ref "JP2") (pin "4") (pinfunction "4_4") (pintype "passive"))
      (node (ref "R42") (pin "2") (pinfunction "2_2") (pintype "passive"))
      (node (ref "U1") (pin "10") (pinfunction "OE_10") (pintype "input"))
      (node (ref "U1") (pin "2") (pinfunction "VCCA_2") (pintype "power_in"))
    )
    (net (code "2") (name "+5V") (class "Default")
      (node (ref "C1") (pin "1") (pinfunction "1_1") (pintype "passive"))
      (node (ref "C18") (pin "+") (pinfunction "+_+") (pintype "passive"))
      (node (ref "C26") (pin "1") (pinfunction "1_1") (pintype "passive"))
      (node (ref "C28") (pin "1") (pinfunction "1_1") (pintype "passive"))
      (node (ref "C34") (pin "1") (pinfunction "1_1") (pintype "passive"))
      (node (ref "C44") (pin "1") (pinfunction "1_1") (pintype "passive"))
      (node (ref "C45") (pin "1") (pinfunction "1_1") (pintype "passive"))
      (node (ref "C8") (pin "2") (pinfunction "2_2") (pintype "passive"))
      (node (ref "D2") (pin "K") (pinfunction "C_K") (pintype "passive"))
      (node (ref "IC2") (pin "16") (pinfunction "VDD_16") (pintype "power_in"))
      (node (ref "IC3") (pin "3") (pinfunction "IN_3") (pintype "input"))
      (node (ref "IC4") (pin "8") (pinfunction "V+_8") (pintype "power_in"))
      (node (ref "L5") (pin "1") (pinfunction "1_1") (pintype "passive"))
      (node (ref "OK2") (pin "8") (pinfunction "COL_8") (pintype "passive"))
      (node (ref "R17") (pin "2") (pinfunction "2_2") (pintype "passive"))
      (node (ref "R26") (pin "2") (pinfunction "2_2") (pintype "passive"))
      (node (ref "R43") (pin "2") (pinfunction "2_2") (pintype "passive"))
      (node (ref "R48") (pin "2") (pinfunction "2_2") (pintype "passive"))
      (node (ref "R_LINE") (pin "1") (pinfunction "1_1") (pintype "passive"))
      (node (ref "S1") (pin "1") (pinfunction "S_1") (pintype "passive"))
      (node (ref "S1") (pin "2") (pinfunction "S1_2") (pintype "passive"))
      (node (ref "SV1") (pin "2") (pinfunction "2_2") (pintype "passive"))
      (node (ref "U$1") (pin "3") (pinfunction "VDD_3") (pintype "power_in"))
      (node (ref "U$2") (pin "4") (pinfunction "VCC_4") (pintype "bidirectional"))
      (node (ref "U1") (pin "19") (pinfunction "VCCB_19") (pintype "power_in"))
      (node (ref "U3") (pin "4") (pinfunction "FB_4") (pintype "input"))
      (node (ref "U5") (pin "14") (pinfunction "VDD_14") (pintype "power_in"))
    )
    (net (code "3") (name "+5V{slash}1") (class "Default")
      (node (ref "C40") (pin "+") (pinfunction "+_+") (pintype "passive"))
      (node (ref "JP3") (pin "2") (pinfunction "2_2") (pintype "passive"))
      (node (ref "L1") (pin "1") (pinfunction "1_1") (pintype "passive"))
      (node (ref "R45") (pin "2") (pinfunction "2_2") (pintype "passive"))
      (node (ref "U$8") (pin "4") (pinfunction "FB_4") (pintype "bidirectional"))
    )
    (net (code "4") (name "+5V{slash}3") (class "Default")
      (node (ref "C39") (pin "1") (pinfunction "1_1") (pintype "passive"))
      (node (ref "C7") (pin "2") (pinfunction "2_2") (pintype "passive"))
      (node (ref "D14") (pin "C") (pinfunction "C_C") (pintype "passive"))
      (node (ref "OK1") (pin "6") (pinfunction "COL_6") (pintype "passive"))
      (node (ref "R27") (pin "2") (pinfunction "2_2") (pintype "passive"))
      (node (ref "R30") (pin "1") (pinfunction "1_1") (pintype "passive"))
      (node (ref "R5") (pin "2") (pinfunction "2_2") (pintype "passive"))
      (node (ref "U$2") (pin "19") (pinfunction "AVCC_19") (pintype "bidirectional"))
    )
    (net (code "5") (name "+5V{slash}4") (class "Default")
      (node (ref "C16") (pin "1") (pinfunction "1_1") (pintype "passive"))
      (node (ref "D12") (pin "C") (pinfunction "C_C") (pintype "passive"))
      (node (ref "OK1") (pin "8") (pinfunction "COL_8") (pintype "passive"))
      (node (ref "R29") (pin "1") (pinfunction "1_1") (pintype "passive"))
      (node (ref "R7") (pin "2") (pinfunction "2_2") (pintype "passive"))
    )
    (net (code "6") (name "+12V") (class "Default")
      (node (ref "C11") (pin "1") (pinfunction "1_1") (pintype "passive"))
      (node (ref "C21") (pin "+") (pinfunction "+_+") (pintype "passive"))
      (node (ref "L6") (pin "1") (pinfunction "1_1") (pintype "passive"))
      (node (ref "R44") (pin "2") (pinfunction "2_2") (pintype "passive"))
      (node (ref "U$3") (pin "12") (pinfunction "VCC_12") (pintype "bidirectional"))
      (node (ref "U4") (pin "4") (pinfunction "FB_4") (pintype "input"))
    )
    (net (code "7") (name "+24V") (class "Default")
      (node (ref "C17") (pin "+") (pinfunction "+_+") (pintype "passive"))
      (node (ref "C20") (pin "+") (pinfunction "+_+") (pintype "passive"))
      (node (ref "C3") (pin "+") (pinfunction "+_+") (pintype "passive"))
      (node (ref "C42") (pin "+") (pinfunction "+_+") (pintype "passive"))
      (node (ref "D1") (pin "K") (pinfunction "C_K") (pintype "passive"))
      (node (ref "F1") (pin "P$1") (pinfunction "1_P$1") (pintype "passive"))
      (node (ref "R30") (pin "2") (pinfunction "2_2") (pintype "passive"))
      (node (ref "U$4") (pin "1") (pinfunction "U_IN_1") (pintype "bidirectional"))
      (node (ref "U$8") (pin "1") (pinfunction "VIN_1") (pintype "bidirectional"))
      (node (ref "U3") (pin "7") (pinfunction "VIN_7") (pintype "power_in"))
      (node (ref "U4") (pin "7") (pinfunction "VIN_7") (pintype "power_in"))
    )
    (net (code "8") (name "ACTIVATE_BOOSTER") (class "Default")
      (node (ref "R24") (pin "1") (pinfunction "1_1") (pintype "passive"))
      (node (ref "R25") (pin "1") (pinfunction "1_1") (pintype "passive"))
      (node (ref "R31") (pin "2") (pinfunction "2_2") (pintype "passive"))
      (node (ref "U$2") (pin "26") (pinfunction "PB5_26") (pintype "bidirectional"))
    )
    (net (code "9") (name "ACTIVATE_SERVO") (class "Default")
      (node (ref "R47") (pin "1") (pinfunction "1_1") (pintype "passive"))
      (node (ref "U$2") (pin "13") (pinfunction "PD5_13") (pintype "bidirectional"))
    )
    (net (code "10") (name "ADC1{slash}SCK_A") (class "Default")
      (node (ref "SV1") (pin "7") (pinfunction "7_7") (pintype "passive"))
      (node (ref "U$2") (pin "12") (pinfunction "(RXD)PD4_12") (pintype "bidirectional"))
    )
    (net (code "11") (name "ADC_CAP") (class "Default")
      (node (ref "C23") (pin "1") (pinfunction "1_1") (pintype "passive"))
      (node (ref "IC4") (pin "3") (pinfunction "+IN_3") (pintype "input"))
      (node (ref "OK1") (pin "5") (pinfunction "EMIT_5") (pintype "passive"))
      (node (ref "R8") (pin "2") (pinfunction "2_2") (pintype "passive"))
      (node (ref "U$2") (pin "14") (pinfunction "PD6_14") (pintype "bidirectional"))
    )
    (net (code "12") (name "BOOSTER_24V") (class "Default")
      (node (ref "Q5") (pin "3") (pinfunction "S_3") (pintype "passive"))
      (node (ref "R12") (pin "2") (pinfunction "2_2") (pintype "passive"))
      (node (ref "R200") (pin "2") (pinfunction "2_2") (pintype "passive"))
      (node (ref "R23") (pin "1") (pinfunction "1_1") (pintype "passive"))
      (node (ref "R46") (pin "2") (pinfunction "2_2") (pintype "passive"))
      (node (ref "X2") (pin "2") (pinfunction "KL_2") (pintype "passive"))
    )
    (net (code "13") (name "BURST") (class "Default")
      (node (ref "D17") (pin "K") (pinfunction "C_K") (pintype "passive"))
      (node (ref "U$2") (pin "18") (pinfunction "PC5_18") (pintype "bidirectional"))
      (node (ref "U5") (pin "6") (pinfunction "OUTB_6") (pintype "output"))
    )
    (net (code "14") (name "CAN_H") (class "Default")
      (node (ref "RJ_1") (pin "P$3") (pinfunction "P$3_P$3") (pintype "bidirectional"))
      (node (ref "RJ_2") (pin "P$3") (pinfunction "P$3_P$3") (pintype "bidirectional"))
      (node (ref "SJ1") (pin "2") (pinfunction "2_2") (pintype "passive"))
      (node (ref "U$1") (pin "7") (pinfunction "CANH_7") (pintype "bidirectional"))
    )
    (net (code "15") (name "CAN_L") (class "Default")
      (node (ref "R32") (pin "2") (pinfunction "2_2") (pintype "passive"))
      (node (ref "RJ_1") (pin "P$2") (pinfunction "P$2_P$2") (pintype "bidirectional"))
      (node (ref "RJ_2") (pin "P$2") (pinfunction "P$2_P$2") (pintype "bidirectional"))
      (node (ref "U$1") (pin "6") (pinfunction "CANL_6") (pintype "bidirectional"))
    )
    (net (code "16") (name "CAN_RX") (class "Default")
      (node (ref "U$1") (pin "4") (pinfunction "RXD_4") (pintype "output"))
      (node (ref "U$2") (pin "7") (pinfunction "(RXCAN)PC3_7") (pintype "bidirectional"))
    )
    (net (code "17") (name "CAN_TX") (class "Default")
      (node (ref "U$1") (pin "1") (pinfunction "TXD_1") (pintype "input"))
      (node (ref "U$2") (pin "6") (pinfunction "(TXCAN)PC2_6") (pintype "bidirectional"))
    )
    (net (code "18") (name "CAP_+12V") (class "Default")
      (node (ref "C29") (pin "+") (pinfunction "+_+") (pintype "passive"))
      (node (ref "C31") (pin "1") (pinfunction "1_1") (pintype "passive"))
      (node (ref "C32") (pin "1") (pinfunction "1_1") (pintype "passive"))
      (node (ref "C43") (pin "1") (pinfunction "1_1") (pintype "passive"))
      (node (ref "IC1") (pin "8") (pinfunction "V+_8") (pintype "power_in"))
      (node (ref "R29") (pin "2") (pinfunction "2_2") (pintype "passive"))
      (node (ref "R39") (pin "2") (pinfunction "2_2") (pintype "passive"))
      (node (ref "R40") (pin "2") (pinfunction "2_2") (pintype "passive"))
      (node (ref "R41") (pin "2") (pinfunction "2_2") (pintype "passive"))
      (node (ref "R49") (pin "2") (pinfunction "2_2") (pintype "passive"))
      (node (ref "U$4") (pin "6") (pinfunction "+U_OUT_6") (pintype "bidirectional"))
      (node (ref "U$5") (pin "8") (pinfunction "VDD_8") (pintype "bidirectional"))
      (node (ref "U$6") (pin "8") (pinfunction "VDD_8") (pintype "bidirectional"))
    )
    (net (code "19") (name "CAP_-12V") (class "Default")
      (node (ref "C30") (pin "-") (pinfunction "-_-") (pintype "passive"))
      (node (ref "C43") (pin "2") (pinfunction "2_2") (pintype "passive"))
      (node (ref "IC1") (pin "4") (pinfunction "V-_4") (pintype "power_in"))
      (node (ref "LED10") (pin "C") (pinfunction "C_C") (pintype "passive"))
      (node (ref "U$4") (pin "4") (pinfunction "-U_OUT_4") (pintype "bidirectional"))
    )
    (net (code "20") (name "CAP_0V") (class "Default")
      (node (ref "C14") (pin "2") (pinfunction "2_2") (pintype "passive"))
      (node (ref "C15") (pin "2") (pinfunction "2_2") (pintype "passive"))
      (node (ref "C16") (pin "2") (pinfunction "2_2") (pintype "passive"))
      (node (ref "C25") (pin "-") (pinfunction "-_-") (pintype "passive"))
      (node (ref "C29") (pin "-") (pinfunction "-_-") (pintype "passive"))
      (node (ref "C30") (pin "+") (pinfunction "+_+") (pintype "passive"))
      (node (ref "C31") (pin "2") (pinfunction "2_2") (pintype "passive"))
      (node (ref "C32") (pin "2") (pinfunction "2_2") (pintype "passive"))
      (node (ref "C46") (pin "2") (pinfunction "2_2") (pintype "passive"))
      (node (ref "CAP_0V") (pin "P$1") (pinfunction "P_P$1") (pintype "passive"))
      (node (ref "D10") (pin "A") (pinfunction "A_A") (pintype "passive"))
      (node (ref "D11") (pin "A") (pinfunction "A_A") (pintype "passive"))
      (node (ref "D12") (pin "A") (pinfunction "A_A") (pintype "passive"))
      (node (ref "D5") (pin "A") (pinfunction "A_A") (pintype "passive"))
      (node (ref "LED9") (pin "C") (pinfunction "C_C") (pintype "passive"))
      (node (ref "OK1") (pin "4") (pinfunction "C_4") (pintype "passive"))
      (node (ref "OK2") (pin "2") (pinfunction "C_2") (pintype "passive"))
      (node (ref "Q2") (pin "S") (pinfunction "S_S") (pintype "passive"))
      (node (ref "Q6") (pin "S") (pinfunction "S_S") (pintype "passive"))
      (node (ref "R11") (pin "1") (pinfunction "1_1") (pintype "passive"))
      (node (ref "R20") (pin "1") (pinfunction "1_1") (pintype "passive"))
      (node (ref "R36") (pin "1") (pinfunction "1_1") (pintype "passive"))
      (node (ref "R37") (pin "1") (pinfunction "1_1") (pintype "passive"))
      (node (ref "R38") (pin "1") (pinfunction "1_1") (pintype "passive"))
      (node (ref "R4") (pin "1") (pinfunction "1_1") (pintype "passive"))
      (node (ref "R50") (pin "2") (pinfunction "2_2") (pintype "passive"))
      (node (ref "R6") (pin "1") (pinfunction "1_1") (pintype "passive"))
      (node (ref "T1") (pin "2") (pinfunction "E_2") (pintype "passive"))
      (node (ref "U$4") (pin "5") (pinfunction "0V_5") (pintype "bidirectional"))
      (node (ref "U$5") (pin "5") (pinfunction "GND_5") (pintype "bidirectional"))
      (node (ref "U$6") (pin "5") (pinfunction "GND_5") (pintype "bidirectional"))
      (node (ref "VR1") (pin "3") (pinfunction "A_3") (pintype "passive"))
      (node (ref "VR2") (pin "3") (pinfunction "A_3") (pintype "passive"))
      (node (ref "VR3") (pin "3") (pinfunction "A_3") (pintype "passive"))
    )
    (net (code "21") (name "CAP_330V") (class "Default")
      (node (ref "C25") (pin "+") (pinfunction "+_+") (pintype "passive"))
      (node (ref "CAP_330V") (pin "P$1") (pinfunction "P_P$1") (pintype "passive"))
      (node (ref "COIL_OUT") (pin "P$1") (pinfunction "P_P$1") (pintype "passive"))
      (node (ref "D8") (pin "K") (pinfunction "C_K") (pintype "passive"))
      (node (ref "D9") (pin "K") (pinfunction "C_K") (pintype "passive"))
      (node (ref "R101") (pin "2") (pinfunction "2_2") (pintype "passive"))
      (node (ref "R16") (pin "2") (pinfunction "2_2") (pintype "passive"))
      (node (ref "R2") (pin "1") (pinfunction "1_1") (pintype "passive"))
      (node (ref "R33") (pin "2") (pinfunction "2_2") (pintype "passive"))
      (node (ref "R34") (pin "2") (pinfunction "2_2") (pintype "passive"))
      (node (ref "R35") (pin "2") (pinfunction "2_2") (pintype "passive"))
      (node (ref "U$7") (pin "C") (pinfunction "C_C") (pintype "passive"))
    )
    (net (code "22") (name "CLKOUT_ETH") (class "Default")
      (node (ref "U1") (pin "12") (pinfunction "B8_12") (pintype "bidirectional"))
    )
    (net (code "23") (name "CLKOUT_ETH_3V") (class "Default")
      (node (ref "JP2") (pin "1") (pinfunction "1_1") (pintype "passive"))
      (node (ref "U1") (pin "9") (pinfunction "A8_9") (pintype "bidirectional"))
    )
    (net (code "24") (name "CS_ETH") (class "Default")
      (node (ref "U$2") (pin "29") (pinfunction "PD0_29") (pintype "bidirectional"))
      (node (ref "U1") (pin "13") (pinfunction "B7_13") (pintype "bidirectional"))
    )
    (net (code "25") (name "CS_ETH_3V") (class "Default")
      (node (ref "JP2") (pin "2") (pinfunction "2_2") (pintype "passive"))
      (node (ref "U1") (pin "8") (pinfunction "A7_8") (pintype "bidirectional"))
    )
    (net (code "26") (name "D2A{slash}RF_MAX") (class "Default")
      (node (ref "RF_MAX") (pin "1") (pinfunction "1_1") (pintype "passive"))
      (node (ref "U$2") (pin "25") (pinfunction "PC7_25") (pintype "bidirectional"))
    )
    (net (code "27") (name "FREI") (class "Default")
      (node (ref "U$2") (pin "16") (pinfunction "PB2_16") (pintype "bidirectional"))
    )
    (net (code "28") (name "FREI2") (class "Default")
      (node (ref "U$2") (pin "27") (pinfunction "PB6_27") (pintype "bidirectional"))
    )
    (net (code "29") (name "FREI3") (class "Default")
      (node (ref "U$2") (pin "15") (pinfunction "PD7_15") (pintype "bidirectional"))
    )
    (net (code "30") (name "GND") (class "Default")
      (node (ref "C1") (pin "2") (pinfunction "2_2") (pintype "passive"))
      (node (ref "C11") (pin "2") (pinfunction "2_2") (pintype "passive"))
      (node (ref "C12") (pin "2") (pinfunction "2_2") (pintype "passive"))
      (node (ref "C17") (pin "-") (pinfunction "-_-") (pintype "passive"))
      (node (ref "C18") (pin "-") (pinfunction "-_-") (pintype "passive"))
      (node (ref "C2") (pin "2") (pinfunction "2_2") (pintype "passive"))
      (node (ref "C20") (pin "-") (pinfunction "-_-") (pintype "passive"))
      (node (ref "C21") (pin "-") (pinfunction "-_-") (pintype "passive"))
      (node (ref "C23") (pin "2") (pinfunction "2_2") (pintype "passive"))
      (node (ref "C24") (pin "2") (pinfunction "2_2") (pintype "passive"))
      (node (ref "C26") (pin "2") (pinfunction "2_2") (pintype "passive"))
      (node (ref "C27") (pin "2") (pinfunction "2_2") (pintype "passive"))
      (node (ref "C28") (pin "2") (pinfunction "2_2") (pintype "passive"))
      (node (ref "C3") (pin "-") (pinfunction "-_-") (pintype "passive"))
      (node (ref "C33") (pin "2") (pinfunction "2_2") (pintype "passive"))
      (node (ref "C34") (pin "2") (pinfunction "2_2") (pintype "passive"))
      (node (ref "C36") (pin "2") (pinfunction "2_2") (pintype "passive"))
      (node (ref "C37") (pin "2") (pinfunction "2_2") (pintype "passive"))
      (node (ref "C38") (pin "2") (pinfunction "2_2") (pintype "passive"))
      (node (ref "C39") (pin "2") (pinfunction "2_2") (pintype "passive"))
      (node (ref "C4") (pin "1") (pinfunction "1_1") (pintype "passive"))
      (node (ref "C40") (pin "-") (pinfunction "-_-") (pintype "passive"))
      (node (ref "C42") (pin "-") (pinfunction "-_-") (pintype "passive"))
      (node (ref "C44") (pin "2") (pinfunction "2_2") (pintype "passive"))
      (node (ref "C45") (pin "2") (pinfunction "2_2") (pintype "passive"))
      (node (ref "C5") (pin "1") (pinfunction "1_1") (pintype "passive"))
      (node (ref "C6") (pin "1") (pinfunction "1_1") (pintype "passive"))
      (node (ref "C7") (pin "1") (pinfunction "1_1") (pintype "passive"))
      (node (ref "C8") (pin "1") (pinfunction "1_1") (pintype "passive"))
      (node (ref "CF") (pin "2") (pinfunction "2_2") (pintype "passive"))
      (node (ref "CSS") (pin "2") (pinfunction "2_2") (pintype "passive"))
      (node (ref "C_DELAY") (pin "2") (pinfunction "2_2") (pintype "passive"))
      (node (ref "C_ISEN_B") (pin "2") (pinfunction "2_2") (pintype "passive"))
      (node (ref "D1") (pin "A") (pinfunction "A_A") (pintype "passive"))
      (node (ref "D14") (pin "A") (pinfunction "A_A") (pintype "passive"))
      (node (ref "D15") (pin "A") (pinfunction "A_A") (pintype "passive"))
      (node (ref "D4") (pin "A") (pinfunction "A_A") (pintype "passive"))
      (node (ref "D6") (pin "A") (pinfunction "A_A") (pintype "passive"))
      (node (ref "D7") (pin "A") (pinfunction "A_A") (pintype "passive"))
      (node (ref "IC2") (pin "3") (pinfunction "R0_3") (pintype "input"))
      (node (ref "IC2") (pin "4") (pinfunction "S0_4") (pintype "input"))
      (node (ref "IC2") (pin "6") (pinfunction "S1_6") (pintype "input"))
      (node (ref "IC2") (pin "7") (pinfunction "R1_7") (pintype "input"))
      (node (ref "IC2") (pin "8") (pinfunction "VSS_8") (pintype "power_in"))
      (node (ref "IC3") (pin "1") (pinfunction "GND_1") (pintype "input"))
      (node (ref "IC4") (pin "4") (pinfunction "V-_4") (pintype "power_in"))
      (node (ref "JP2") (pin "5") (pinfunction "5_5") (pintype "passive"))
      (node (ref "LED4") (pin "C") (pinfunction "C_C") (pintype "passive"))
      (node (ref "LED5") (pin "C") (pinfunction "C_C") (pintype "passive"))
      (node (ref "LED6") (pin "C") (pinfunction "C_C") (pintype "passive"))
      (node (ref "LED7") (pin "C") (pinfunction "C_C") (pintype "passive"))
      (node (ref "R1") (pin "1") (pinfunction "1_1") (pintype "passive"))
      (node (ref "R10") (pin "1") (pinfunction "1_1") (pintype "passive"))
      (node (ref "R13") (pin "1") (pinfunction "1_1") (pintype "passive"))
      (node (ref "R21") (pin "1") (pinfunction "1_1") (pintype "passive"))
      (node (ref "R22") (pin "1") (pinfunction "1_1") (pintype "passive"))
      (node (ref "R28") (pin "1") (pinfunction "1_1") (pintype "passive"))
      (node (ref "R31") (pin "1") (pinfunction "1_1") (pintype "passive"))
      (node (ref "R51") (pin "1") (pinfunction "1_1") (pintype "passive"))
      (node (ref "R8") (pin "1") (pinfunction "1_1") (pintype "passive"))
      (node (ref "RF_MIN") (pin "1") (pinfunction "1_1") (pintype "passive"))
      (node (ref "RJ_1") (pin "P$4") (pinfunction "P$4_P$4") (pintype "bidirectional"))
      (node (ref "R_DELAY") (pin "1") (pinfunction "1_1") (pintype "passive"))
      (node (ref "R_ISEN_B") (pin "1") (pinfunction "1_1") (pintype "passive"))
      (node (ref "SV1") (pin "10") (pinfunction "10_10") (pintype "passive"))
      (node (ref "SV1") (pin "4") (pinfunction "4_4") (pintype "passive"))
      (node (ref "SV1") (pin "6") (pinfunction "6_6") (pintype "passive"))
      (node (ref "SV1") (pin "8") (pinfunction "8_8") (pintype "passive"))
      (node (ref "T2") (pin "2") (pinfunction "E_2") (pintype "passive"))
      (node (ref "T4") (pin "2") (pinfunction "E_2") (pintype "passive"))
      (node (ref "T5") (pin "2") (pinfunction "S_2") (pintype "passive"))
      (node (ref "U$1") (pin "2") (pinfunction "VSS_2") (pintype "passive"))
      (node (ref "U$2") (pin "20") (pinfunction "AGND_20") (pintype "power_in"))
      (node (ref "U$2") (pin "5") (pinfunction "GND_5") (pintype "power_in"))
      (node (ref "U$3") (pin "10") (pinfunction "GND_10") (pintype "bidirectional"))
      (node (ref "U$3") (pin "8") (pinfunction "DIS_8") (pintype "bidirectional"))
      (node (ref "U$4") (pin "2") (pinfunction "GND_2") (pintype "bidirectional"))
      (node (ref "U$5") (pin "1") (pinfunction "NC_1") (pintype "bidirectional"))
      (node (ref "U$5") (pin "3") (pinfunction "CATHODE_3") (pintype "bidirectional"))
      (node (ref "U$5") (pin "4") (pinfunction "NC_4") (pintype "bidirectional"))
      (node (ref "U$6") (pin "1") (pinfunction "NC_1") (pintype "bidirectional"))
      (node (ref "U$6") (pin "4") (pinfunction "NC_4") (pintype "bidirectional"))
      (node (ref "U$8") (pin "3") (pinfunction "GND_3") (pintype "bidirectional"))
      (node (ref "U$8") (pin "5") (pinfunction "~{ON}/OFF_5") (pintype "bidirectional"))
      (node (ref "U1") (pin "11") (pinfunction "GND_11") (pintype "passive"))
      (node (ref "U3") (pin "6") (pinfunction "GND_6") (pintype "passive"))
      (node (ref "U4") (pin "6") (pinfunction "GND_6") (pintype "passive"))
      (node (ref "U5") (pin "11") (pinfunction "IN_1C_11") (pintype "input"))
      (node (ref "U5") (pin "13") (pinfunction "IN_3C_13") (pintype "input"))
      (node (ref "U5") (pin "5") (pinfunction "IN_3B_5") (pintype "input"))
      (node (ref "U5") (pin "7") (pinfunction "VSS_7") (pintype "passive"))
      (node (ref "U5") (pin "8") (pinfunction "IN_3A_8") (pintype "input"))
      (node (ref "X1") (pin "2") (pinfunction "KL_2") (pintype "passive"))
    )
    (net (code "31") (name "GND1") (class "Default")
      (node (ref "C10") (pin "-") (pinfunction "-_-") (pintype "passive"))
      (node (ref "C13") (pin "2") (pinfunction "2_2") (pintype "passive"))
      (node (ref "C35") (pin "2") (pinfunction "2_2") (pintype "passive"))
      (node (ref "C41") (pin "2") (pinfunction "2_2") (pintype "passive"))
      (node (ref "C9") (pin "-") (pinfunction "-_-") (pintype "passive"))
      (node (ref "LED8") (pin "C") (pinfunction "C_C") (pintype "passive"))
      (node (ref "Q4") (pin "S") (pinfunction "S_S") (pintype "passive"))
      (node (ref "R54") (pin "2") (pinfunction "2_2") (pintype "passive"))
      (node (ref "T3") (pin "2") (pinfunction "E_2") (pintype "passive"))
      (node (ref "X2") (pin "1") (pinfunction "KL_1") (pintype "passive"))
    )
    (net (code "32") (name "INT_ETH") (class "Default")
      (node (ref "U$2") (pin "30") (pinfunction "PC0_30") (pintype "bidirectional"))
      (node (ref "U1") (pin "20") (pinfunction "B1_20") (pintype "bidirectional"))
    )
    (net (code "33") (name "INT_ETH_3V") (class "Default")
      (node (ref "JP1") (pin "5") (pinfunction "5_5") (pintype "passive"))
      (node (ref "U1") (pin "1") (pinfunction "A1_1") (pintype "bidirectional"))
    )
    (net (code "34") (name "KICK") (class "Default")
      (node (ref "R19") (pin "1") (pinfunction "1_1") (pintype "passive"))
      (node (ref "U$2") (pin "23") (pinfunction "PB3_23") (pintype "bidirectional"))
    )
    (net (code "35") (name "MISO") (class "Default")
      (node (ref "U$2") (pin "8") (pinfunction "PB0_8") (pintype "bidirectional"))
      (node (ref "U1") (pin "17") (pinfunction "B3_17") (pintype "bidirectional"))
    )
    (net (code "36") (name "MISO_3V") (class "Default")
      (node (ref "JP1") (pin "3") (pinfunction "3_3") (pintype "passive"))
      (node (ref "U1") (pin "4") (pinfunction "A3_4") (pintype "bidirectional"))
    )
    (net (code "37") (name "MOSI") (class "Default")
      (node (ref "U$2") (pin "9") (pinfunction "PB1_9") (pintype "bidirectional"))
      (node (ref "U1") (pin "16") (pinfunction "B4_16") (pintype "bidirectional"))
    )
    (net (code "38") (name "MOSI_3V") (class "Default")
      (node (ref "JP1") (pin "2") (pinfunction "2_2") (pintype "passive"))
      (node (ref "U1") (pin "5") (pinfunction "A4_5") (pintype "bidirectional"))
    )
    (net (code "39") (name "NOTAUS") (class "Default")
      (node (ref "D16") (pin "K") (pinfunction "C_K") (pintype "passive"))
      (node (ref "R14") (pin "1") (pinfunction "1_1") (pintype "passive"))
      (node (ref "U$2") (pin "22") (pinfunction "PC6_22") (pintype "bidirectional"))
      (node (ref "U5") (pin "9") (pinfunction "OUTA_9") (pintype "output"))
    )
    (net (code "40") (name "Net-(COIL_IN-P)") (class "Default")
      (node (ref "COIL_IN") (pin "P$1") (pinfunction "P_P$1") (pintype "passive"))
      (node (ref "Q2") (pin "D") (pinfunction "D_D") (pintype "passive"))
      (node (ref "R20") (pin "2") (pinfunction "2_2") (pintype "passive"))
      (node (ref "U$7") (pin "A") (pinfunction "A_A") (pintype "passive"))
    )
    (net (code "41") (name "Net-(CSS-Pad1)") (class "Default")
      (node (ref "CSS") (pin "1") (pinfunction "1_1") (pintype "passive"))
      (node (ref "R_SS") (pin "1") (pinfunction "1_1") (pintype "passive"))
      (node (ref "R_SS2") (pin "1") (pinfunction "1_1") (pintype "passive"))
    )
    (net (code "42") (name "Net-(C_ISEN_A-Pad1)") (class "Default")
      (node (ref "C_ISEN_A") (pin "1") (pinfunction "1_1") (pintype "passive"))
      (node (ref "R_ISEN_A") (pin "2") (pinfunction "2_2") (pintype "passive"))
    )
    (net (code "43") (name "Net-(D3-PadA)") (class "Default")
      (node (ref "D3") (pin "A") (pinfunction "A_A") (pintype "passive"))
      (node (ref "D4") (pin "C") (pinfunction "C_C") (pintype "passive"))
      (node (ref "R_ISEN_A") (pin "1") (pinfunction "1_1") (pintype "passive"))
    )
    (net (code "44") (name "Net-(D6-C)") (class "Default")
      (node (ref "C19") (pin "2") (pinfunction "2_2") (pintype "passive"))
      (node (ref "D6") (pin "K") (pinfunction "C_K") (pintype "passive"))
      (node (ref "L5") (pin "2") (pinfunction "2_2") (pintype "passive"))
      (node (ref "U3") (pin "8") (pinfunction "VSW_8") (pintype "output"))
    )
    (net (code "45") (name "Net-(D7-C)") (class "Default")
      (node (ref "C22") (pin "2") (pinfunction "2_2") (pintype "passive"))
      (node (ref "D7") (pin "K") (pinfunction "C_K") (pintype "passive"))
      (node (ref "L6") (pin "2") (pinfunction "2_2") (pintype "passive"))
      (node (ref "U4") (pin "8") (pinfunction "VSW_8") (pintype "output"))
    )
    (net (code "46") (name "Net-(D10-C)") (class "Default")
      (node (ref "D10") (pin "K") (pinfunction "C_K") (pintype "passive"))
      (node (ref "D8") (pin "A") (pinfunction "A_A") (pintype "passive"))
      (node (ref "L7") (pin "2") (pinfunction "8_2") (pintype "passive"))
    )
    (net (code "47") (name "Net-(D11-C)") (class "Default")
      (node (ref "D11") (pin "K") (pinfunction "C_K") (pintype "passive"))
      (node (ref "D9") (pin "A") (pinfunction "A_A") (pintype "passive"))
      (node (ref "L7") (pin "4") (pinfunction "1_4") (pintype "passive"))
    )
    (net (code "48") (name "Net-(D15-C)") (class "Default")
      (node (ref "D15") (pin "K") (pinfunction "C_K") (pintype "passive"))
      (node (ref "L1") (pin "2") (pinfunction "2_2") (pintype "passive"))
      (node (ref "U$8") (pin "2") (pinfunction "VOUT_2") (pintype "bidirectional"))
    )
    (net (code "49") (name "Net-(F1-2)") (class "Default")
      (node (ref "F1") (pin "P$2") (pinfunction "2_P$2") (pintype "passive"))
      (node (ref "X1") (pin "1") (pinfunction "KL_1") (pintype "passive"))
    )
    (net (code "50") (name "Net-(IC1A-+IN)") (class "Default")
      (node (ref "C15") (pin "1") (pinfunction "1_1") (pintype "passive"))
      (node (ref "IC1") (pin "3") (pinfunction "+IN_3") (pintype "input"))
      (node (ref "IC1") (pin "5") (pinfunction "+IN_5") (pintype "input"))
      (node (ref "R101") (pin "1") (pinfunction "1_1") (pintype "passive"))
      (node (ref "R6") (pin "2") (pinfunction "2_2") (pintype "passive"))
    )
    (net (code "51") (name "Net-(IC1A--IN)") (class "Default")
      (node (ref "C14") (pin "1") (pinfunction "1_1") (pintype "passive"))
      (node (ref "IC1") (pin "2") (pinfunction "-IN_2") (pintype "input"))
      (node (ref "OK1") (pin "7") (pinfunction "EMIT_7") (pintype "passive"))
      (node (ref "R11") (pin "2") (pinfunction "2_2") (pintype "passive"))
    )
    (net (code "52") (name "Net-(IC1A-OUT)") (class "Default")
      (node (ref "IC1") (pin "1") (pinfunction "OUT_1") (pintype "output"))
      (node (ref "R105") (pin "1") (pinfunction "1_1") (pintype "passive"))
    )
    (net (code "53") (name "Net-(IC1B--IN)") (class "Default")
      (node (ref "C46") (pin "1") (pinfunction "1_1") (pintype "passive"))
      (node (ref "IC1") (pin "6") (pinfunction "-IN_6") (pintype "input"))
      (node (ref "R4") (pin "2") (pinfunction "2_2") (pintype "passive"))
      (node (ref "R7") (pin "1") (pinfunction "1_1") (pintype "passive"))
    )
    (net (code "54") (name "Net-(IC1B-OUT)") (class "Default")
      (node (ref "IC1") (pin "7") (pinfunction "OUT_7") (pintype "output"))
      (node (ref "R9") (pin "1") (pinfunction "1_1") (pintype "passive"))
    )
    (net (code "55") (name "Net-(IC2A-Q2)") (class "Default")
      (node (ref "IC2") (pin "10") (pinfunction "Q2_10") (pintype "output"))
      (node (ref "U5") (pin "1") (pinfunction "IN_1A_1") (pintype "input"))
    )
    (net (code "56") (name "Net-(IC2A-Q3)") (class "Default")
      (node (ref "IC2") (pin "1") (pinfunction "Q3_1") (pintype "output"))
      (node (ref "U5") (pin "3") (pinfunction "IN_1B_3") (pintype "input"))
    )
    (net (code "57") (name "Net-(IC4A--IN)") (class "Default")
      (node (ref "C36") (pin "1") (pinfunction "1_1") (pintype "passive"))
      (node (ref "IC4") (pin "2") (pinfunction "-IN_2") (pintype "input"))
      (node (ref "R21") (pin "2") (pinfunction "2_2") (pintype "passive"))
      (node (ref "R5") (pin "1") (pinfunction "1_1") (pintype "passive"))
      (node (ref "R52") (pin "2") (pinfunction "2_2") (pintype "passive"))
    )
    (net (code "58") (name "Net-(IC4A-OUT)") (class "Default")
      (node (ref "IC4") (pin "1") (pinfunction "OUT_1") (pintype "output"))
      (node (ref "U5") (pin "4") (pinfunction "IN_2B_4") (pintype "input"))
    )
    (net (code "59") (name "Net-(IC4B-+IN)") (class "Default")
      (node (ref "C37") (pin "1") (pinfunction "1_1") (pintype "passive"))
      (node (ref "IC4") (pin "5") (pinfunction "+IN_5") (pintype "input"))
      (node (ref "R27") (pin "1") (pinfunction "1_1") (pintype "passive"))
      (node (ref "R28") (pin "2") (pinfunction "2_2") (pintype "passive"))
    )
    (net (code "60") (name "Net-(IC4B--IN)") (class "Default")
      (node (ref "C38") (pin "1") (pinfunction "1_1") (pintype "passive"))
      (node (ref "IC4") (pin "6") (pinfunction "-IN_6") (pintype "input"))
      (node (ref "R12") (pin "1") (pinfunction "1_1") (pintype "passive"))
      (node (ref "R13") (pin "2") (pinfunction "2_2") (pintype "passive"))
    )
    (net (code "61") (name "Net-(IC4B-OUT)") (class "Default")
      (node (ref "IC4") (pin "7") (pinfunction "OUT_7") (pintype "output"))
      (node (ref "U5") (pin "12") (pinfunction "IN_2C_12") (pintype "input"))
    )
    (net (code "62") (name "Net-(L7-4)") (class "Default")
      (node (ref "L3") (pin "1") (pinfunction "1_1") (pintype "passive"))
      (node (ref "L4") (pin "1") (pinfunction "1_1") (pintype "passive"))
      (node (ref "L7") (pin "9") (pinfunction "4_9") (pintype "passive"))
    )
    (net (code "63") (name "Net-(L7-5)") (class "Default")
      (node (ref "C13") (pin "1") (pinfunction "1_1") (pintype "passive"))
      (node (ref "C41") (pin "1") (pinfunction "1_1") (pintype "passive"))
      (node (ref "C_ISEN_A") (pin "2") (pinfunction "2_2") (pintype "passive"))
      (node (ref "L3") (pin "2") (pinfunction "2_2") (pintype "passive"))
      (node (ref "L7") (pin "11") (pinfunction "5_11") (pintype "passive"))
    )
    (net (code "64") (name "Net-(LED1-PadA)") (class "Default")
      (node (ref "LED1") (pin "A") (pinfunction "A_A") (pintype "passive"))
      (node (ref "R39") (pin "1") (pinfunction "1_1") (pintype "passive"))
    )
    (net (code "65") (name "Net-(LED2-PadA)") (class "Default")
      (node (ref "LED2") (pin "A") (pinfunction "A_A") (pintype "passive"))
      (node (ref "R40") (pin "1") (pinfunction "1_1") (pintype "passive"))
    )
    (net (code "66") (name "Net-(LED3-PadA)") (class "Default")
      (node (ref "LED3") (pin "A") (pinfunction "A_A") (pintype "passive"))
      (node (ref "R41") (pin "1") (pinfunction "1_1") (pintype "passive"))
    )
    (net (code "67") (name "Net-(LED4-PadA)") (class "Default")
      (node (ref "LED4") (pin "A") (pinfunction "A_A") (pintype "passive"))
      (node (ref "R42") (pin "1") (pinfunction "1_1") (pintype "passive"))
    )
    (net (code "68") (name "Net-(LED5-PadA)") (class "Default")
      (node (ref "LED5") (pin "A") (pinfunction "A_A") (pintype "passive"))
      (node (ref "R43") (pin "1") (pinfunction "1_1") (pintype "passive"))
    )
    (net (code "69") (name "Net-(LED6-PadA)") (class "Default")
      (node (ref "LED6") (pin "A") (pinfunction "A_A") (pintype "passive"))
      (node (ref "R44") (pin "1") (pinfunction "1_1") (pintype "passive"))
    )
    (net (code "70") (name "Net-(LED7-PadA)") (class "Default")
      (node (ref "LED7") (pin "A") (pinfunction "A_A") (pintype "passive"))
      (node (ref "R45") (pin "1") (pinfunction "1_1") (pintype "passive"))
    )
    (net (code "71") (name "Net-(LED8-PadA)") (class "Default")
      (node (ref "LED8") (pin "A") (pinfunction "A_A") (pintype "passive"))
      (node (ref "R46") (pin "1") (pinfunction "1_1") (pintype "passive"))
    )
    (net (code "72") (name "Net-(LED9-PadA)") (class "Default")
      (node (ref "LED9") (pin "A") (pinfunction "A_A") (pintype "passive"))
      (node (ref "R49") (pin "1") (pinfunction "1_1") (pintype "passive"))
    )
    (net (code "73") (name "Net-(LED10-PadA)") (class "Default")
      (node (ref "LED10") (pin "A") (pinfunction "A_A") (pintype "passive"))
      (node (ref "R50") (pin "1") (pinfunction "1_1") (pintype "passive"))
    )
    (net (code "74") (name "Net-(OK1A-A)") (class "Default")
      (node (ref "OK1") (pin "1") (pinfunction "A_1") (pintype "passive"))
      (node (ref "R105") (pin "2") (pinfunction "2_2") (pintype "passive"))
    )
    (net (code "75") (name "Net-(OK1A-C)") (class "Default")
      (node (ref "OK1") (pin "2") (pinfunction "C_2") (pintype "passive"))
      (node (ref "OK1") (pin "3") (pinfunction "A_3") (pintype "passive"))
    )
    (net (code "76") (name "Net-(OK2A-A)") (class "Default")
      (node (ref "OK2") (pin "1") (pinfunction "A_1") (pintype "passive"))
      (node (ref "R9") (pin "2") (pinfunction "2_2") (pintype "passive"))
    )
    (net (code "77") (name "Net-(Q2-PadG)") (class "Default")
      (node (ref "Q2") (pin "G") (pinfunction "G_G") (pintype "passive"))
      (node (ref "R18") (pin "2") (pinfunction "2_2") (pintype "passive"))
    )
    (net (code "78") (name "Net-(Q5-D)") (class "Default")
      (node (ref "C10") (pin "+") (pinfunction "+_+") (pintype "passive"))
      (node (ref "C35") (pin "1") (pinfunction "1_1") (pintype "passive"))
      (node (ref "C9") (pin "+") (pinfunction "+_+") (pintype "passive"))
      (node (ref "Q3") (pin "D") (pinfunction "D_D") (pintype "passive"))
      (node (ref "Q5") (pin "4") (pinfunction "D_4") (pintype "passive"))
      (node (ref "R23") (pin "2") (pinfunction "2_2") (pintype "passive"))
    )
    (net (code "79") (name "Net-(Q5-G)") (class "Default")
      (node (ref "D13") (pin "C") (pinfunction "C_C") (pintype "passive"))
      (node (ref "Q5") (pin "1") (pinfunction "G_1") (pintype "passive"))
      (node (ref "R200") (pin "1") (pinfunction "1_1") (pintype "passive"))
    )
    (net (code "80") (name "Net-(Q6-PadD)") (class "Default")
      (node (ref "Q6") (pin "D") (pinfunction "D_D") (pintype "passive"))
      (node (ref "R3") (pin "2") (pinfunction "2_2") (pintype "passive"))
    )
    (net (code "81") (name "Net-(R2-Pad2)") (class "Default")
      (node (ref "R2") (pin "2") (pinfunction "2_2") (pintype "passive"))
      (node (ref "R3") (pin "1") (pinfunction "1_1") (pintype "passive"))
    )
    (net (code "82") (name "Net-(R15-Pad1)") (class "Default")
      (node (ref "R15") (pin "1") (pinfunction "1_1") (pintype "passive"))
      (node (ref "U$5") (pin "6") (pinfunction "VO_6") (pintype "bidirectional"))
      (node (ref "U$5") (pin "7") (pinfunction "VO_7") (pintype "bidirectional"))
    )
    (net (code "83") (name "Net-(R18-Pad1)") (class "Default")
      (node (ref "R18") (pin "1") (pinfunction "1_1") (pintype "passive"))
      (node (ref "U$6") (pin "6") (pinfunction "VO_6") (pintype "bidirectional"))
      (node (ref "U$6") (pin "7") (pinfunction "VO_7") (pintype "bidirectional"))
    )
    (net (code "84") (name "Net-(R32-Pad1)") (class "Default")
      (node (ref "R32") (pin "1") (pinfunction "1_1") (pintype "passive"))
      (node (ref "SJ1") (pin "1") (pinfunction "1_1") (pintype "passive"))
    )
    (net (code "85") (name "Net-(T1-B)") (class "Default")
      (node (ref "R15") (pin "2") (pinfunction "2_2") (pintype "passive"))
      (node (ref "T1") (pin "1") (pinfunction "B_1") (pintype "passive"))
    )
    (net (code "86") (name "Net-(T1-C)") (class "Default")
      (node (ref "D5") (pin "C") (pinfunction "C_C") (pintype "passive"))
      (node (ref "Q6") (pin "G") (pinfunction "G_G") (pintype "passive"))
      (node (ref "R16") (pin "1") (pinfunction "1_1") (pintype "passive"))
      (node (ref "T1") (pin "3") (pinfunction "C_3") (pintype "passive"))
    )
    (net (code "87") (name "Net-(T2-B)") (class "Default")
      (node (ref "R19") (pin "2") (pinfunction "2_2") (pintype "passive"))
      (node (ref "R51") (pin "2") (pinfunction "2_2") (pintype "passive"))
      (node (ref "T2") (pin "1") (pinfunction "B_1") (pintype "passive"))
    )
    (net (code "88") (name "Net-(T2-C)") (class "Default")
      (node (ref "T2") (pin "3") (pinfunction "C_3") (pintype "passive"))
      (node (ref "U$6") (pin "3") (pinfunction "CATHODE_3") (pintype "bidirectional"))
    )
    (net (code "89") (name "Net-(T3-B)") (class "Default")
      (node (ref "R24") (pin "2") (pinfunction "2_2") (pintype "passive"))
      (node (ref "T3") (pin "1") (pinfunction "B_1") (pintype "passive"))
    )
    (net (code "90") (name "Net-(T3-C)") (class "Default")
      (node (ref "D13") (pin "A") (pinfunction "A_A") (pintype "passive"))
      (node (ref "T3") (pin "3") (pinfunction "C_3") (pintype "passive"))
    )
    (net (code "91") (name "Net-(T4-B)") (class "Default")
      (node (ref "R25") (pin "2") (pinfunction "2_2") (pintype "passive"))
      (node (ref "T4") (pin "1") (pinfunction "B_1") (pintype "passive"))
    )
    (net (code "92") (name "Net-(T4-C)") (class "Default")
      (node (ref "R26") (pin "1") (pinfunction "1_1") (pintype "passive"))
      (node (ref "T4") (pin "3") (pinfunction "C_3") (pintype "passive"))
      (node (ref "U5") (pin "2") (pinfunction "IN_2A_2") (pintype "input"))
    )
    (net (code "93") (name "Net-(T5-D)") (class "Default")
      (node (ref "JP3") (pin "3") (pinfunction "3_3") (pintype "passive"))
      (node (ref "T5") (pin "1") (pinfunction "D_1") (pintype "passive"))
    )
    (net (code "94") (name "Net-(T5-G)") (class "Default")
      (node (ref "R47") (pin "2") (pinfunction "2_2") (pintype "passive"))
      (node (ref "T5") (pin "3") (pinfunction "G_3") (pintype "passive"))
    )
    (net (code "95") (name "Net-(U$1-RS)") (class "Default")
      (node (ref "R1") (pin "2") (pinfunction "2_2") (pintype "passive"))
      (node (ref "U$1") (pin "8") (pinfunction "RS_8") (pintype "input"))
    )
    (net (code "96") (name "Net-(U$2-AREF)") (class "Default")
      (node (ref "C6") (pin "2") (pinfunction "2_2") (pintype "passive"))
      (node (ref "U$2") (pin "21") (pinfunction "AREF_21") (pintype "bidirectional"))
    )
    (net (code "97") (name "Net-(U$2-PE1(XTAL1))") (class "Default")
      (node (ref "C5") (pin "2") (pinfunction "2_2") (pintype "passive"))
      (node (ref "Q1") (pin "1") (pinfunction "1_1") (pintype "passive"))
      (node (ref "U$2") (pin "10") (pinfunction "PE1(XTAL1)_10") (pintype "bidirectional"))
    )
    (net (code "98") (name "Net-(U$2-PE2(XTAL2))") (class "Default")
      (node (ref "C4") (pin "2") (pinfunction "2_2") (pintype "passive"))
      (node (ref "Q1") (pin "2") (pinfunction "2_2") (pintype "passive"))
      (node (ref "U$2") (pin "11") (pinfunction "PE2(XTAL2)_11") (pintype "bidirectional"))
    )
    (net (code "99") (name "Net-(U$3-CF)") (class "Default")
      (node (ref "CF") (pin "1") (pinfunction "1_1") (pintype "passive"))
      (node (ref "U$3") (pin "3") (pinfunction "CF_3") (pintype "bidirectional"))
    )
    (net (code "100") (name "Net-(U$3-CSS)") (class "Default")
      (node (ref "R_SS2") (pin "2") (pinfunction "2_2") (pintype "passive"))
      (node (ref "U$3") (pin "1") (pinfunction "CSS_1") (pintype "bidirectional"))
    )
    (net (code "101") (name "Net-(U$3-DELAY)") (class "Default")
      (node (ref "C_DELAY") (pin "1") (pinfunction "1_1") (pintype "passive"))
      (node (ref "R_DELAY") (pin "2") (pinfunction "2_2") (pintype "passive"))
      (node (ref "U$3") (pin "2") (pinfunction "DELAY_2") (pintype "bidirectional"))
    )
    (net (code "102") (name "Net-(U$3-HVG)") (class "Default")
      (node (ref "Q3") (pin "G") (pinfunction "G_G") (pintype "passive"))
      (node (ref "R53") (pin "1") (pinfunction "1_1") (pintype "passive"))
      (node (ref "U$3") (pin "15") (pinfunction "HVG_15") (pintype "bidirectional"))
    )
    (net (code "103") (name "Net-(U$3-ISEN)") (class "Default")
      (node (ref "C_ISEN_B") (pin "1") (pinfunction "1_1") (pintype "passive"))
      (node (ref "D3") (pin "C") (pinfunction "C_C") (pintype "passive"))
      (node (ref "R_ISEN_B") (pin "2") (pinfunction "2_2") (pintype "passive"))
      (node (ref "U$3") (pin "6") (pinfunction "ISEN_6") (pintype "bidirectional"))
    )
    (net (code "104") (name "Net-(U$3-LINE)") (class "Default")
      (node (ref "R_LINE") (pin "2") (pinfunction "2_2") (pintype "passive"))
      (node (ref "U$3") (pin "7") (pinfunction "LINE_7") (pintype "bidirectional"))
    )
    (net (code "105") (name "Net-(U$3-LVG)") (class "Default")
      (node (ref "Q4") (pin "G") (pinfunction "G_G") (pintype "passive"))
      (node (ref "R54") (pin "1") (pinfunction "1_1") (pintype "passive"))
      (node (ref "U$3") (pin "11") (pinfunction "LVG_11") (pintype "bidirectional"))
    )
    (net (code "106") (name "Net-(U$3-OUT)") (class "Default")
      (node (ref "C_BOOT") (pin "2") (pinfunction "2_2") (pintype "passive"))
      (node (ref "L4") (pin "2") (pinfunction "2_2") (pintype "passive"))
      (node (ref "Q3") (pin "S") (pinfunction "S_S") (pintype "passive"))
      (node (ref "Q4") (pin "D") (pinfunction "D_D") (pintype "passive"))
      (node (ref "R53") (pin "2") (pinfunction "2_2") (pintype "passive"))
      (node (ref "U$3") (pin "14") (pinfunction "OUT_14") (pintype "bidirectional"))
    )
    (net (code "107") (name "Net-(U$3-RFMIN)") (class "Default")
      (node (ref "RF_MAX") (pin "2") (pinfunction "2_2") (pintype "passive"))
      (node (ref "RF_MIN") (pin "2") (pinfunction "2_2") (pintype "passive"))
      (node (ref "R_SS") (pin "2") (pinfunction "2_2") (pintype "passive"))
      (node (ref "U$3") (pin "4") (pinfunction "RFMIN_4") (pintype "bidirectional"))
    )
    (net (code "108") (name "Net-(U$3-VBOOT)") (class "Default")
      (node (ref "C_BOOT") (pin "1") (pinfunction "1_1") (pintype "passive"))
      (node (ref "U$3") (pin "16") (pinfunction "VBOOT_16") (pintype "bidirectional"))
    )
    (net (code "109") (name "Net-(U$5-ANODE)") (class "Default")
      (node (ref "R14") (pin "2") (pinfunction "2_2") (pintype "passive"))
      (node (ref "U$5") (pin "2") (pinfunction "ANODE_2") (pintype "bidirectional"))
    )
    (net (code "110") (name "Net-(U$6-ANODE)") (class "Default")
      (node (ref "R17") (pin "1") (pinfunction "1_1") (pintype "passive"))
      (node (ref "U$6") (pin "2") (pinfunction "ANODE_2") (pintype "bidirectional"))
    )
    (net (code "111") (name "Net-(U3-CB)") (class "Default")
      (node (ref "C19") (pin "1") (pinfunction "1_1") (pintype "passive"))
      (node (ref "U3") (pin "1") (pinfunction "CB_1") (pintype "input"))
    )
    (net (code "112") (name "Net-(U4-CB)") (class "Default")
      (node (ref "C22") (pin "1") (pinfunction "1_1") (pintype "passive"))
      (node (ref "U4") (pin "1") (pinfunction "CB_1") (pintype "input"))
    )
    (net (code "113") (name "Net-(VR1-C)") (class "Default")
      (node (ref "LED1") (pin "C") (pinfunction "C_C") (pintype "passive"))
      (node (ref "VR1") (pin "1") (pinfunction "C_1") (pintype "passive"))
    )
    (net (code "114") (name "Net-(VR1-R)") (class "Default")
      (node (ref "R33") (pin "1") (pinfunction "1_1") (pintype "passive"))
      (node (ref "R36") (pin "2") (pinfunction "2_2") (pintype "passive"))
      (node (ref "VR1") (pin "2") (pinfunction "R_2") (pintype "passive"))
    )
    (net (code "115") (name "Net-(VR2-C)") (class "Default")
      (node (ref "LED2") (pin "C") (pinfunction "C_C") (pintype "passive"))
      (node (ref "VR2") (pin "1") (pinfunction "C_1") (pintype "passive"))
    )
    (net (code "116") (name "Net-(VR2-R)") (class "Default")
      (node (ref "R34") (pin "1") (pinfunction "1_1") (pintype "passive"))
      (node (ref "R37") (pin "2") (pinfunction "2_2") (pintype "passive"))
      (node (ref "VR2") (pin "2") (pinfunction "R_2") (pintype "passive"))
    )
    (net (code "117") (name "Net-(VR3-C)") (class "Default")
      (node (ref "LED3") (pin "C") (pinfunction "C_C") (pintype "passive"))
      (node (ref "VR3") (pin "1") (pinfunction "C_1") (pintype "passive"))
    )
    (net (code "118") (name "Net-(VR3-R)") (class "Default")
      (node (ref "R35") (pin "1") (pinfunction "1_1") (pintype "passive"))
      (node (ref "R38") (pin "2") (pinfunction "2_2") (pintype "passive"))
      (node (ref "VR3") (pin "2") (pinfunction "R_2") (pintype "passive"))
    )
    (net (code "119") (name "OC0A{slash}MOSI_A") (class "Default")
      (node (ref "SV1") (pin "1") (pinfunction "1_1") (pintype "passive"))
    )
    (net (code "120") (name "OC0A{slash}MOSI_A{slash}KICK_VOLTAGE") (class "Default")
      (node (ref "R52") (pin "1") (pinfunction "1_1") (pintype "passive"))
      (node (ref "U$2") (pin "2") (pinfunction "(MOSI_A/TXD)PD3_2") (pintype "bidirectional"))
    )
    (net (code "121") (name "OC1A{slash}MISO_A") (class "Default")
      (node (ref "SV1") (pin "9") (pinfunction "9_9") (pintype "passive"))
      (node (ref "U$2") (pin "1") (pinfunction "(MISO_A)PD2_1") (pintype "bidirectional"))
    )
    (net (code "122") (name "RESET_NOTAUS") (class "Default")
      (node (ref "IC2") (pin "11") (pinfunction "R2_11") (pintype "input"))
      (node (ref "IC2") (pin "15") (pinfunction "R3_15") (pintype "input"))
      (node (ref "U$2") (pin "24") (pinfunction "PB4_24") (pintype "bidirectional"))
    )
    (net (code "123") (name "RST") (class "Default")
      (node (ref "SV1") (pin "5") (pinfunction "5_5") (pintype "passive"))
      (node (ref "U$2") (pin "31") (pinfunction "PE0(RESET)_31") (pintype "input"))
    )
    (net (code "124") (name "RST_ETH") (class "Default")
      (node (ref "U$2") (pin "32") (pinfunction "PD1_32") (pintype "bidirectional"))
      (node (ref "U1") (pin "14") (pinfunction "B6_14") (pintype "bidirectional"))
    )
    (net (code "125") (name "RST_ETH_3V") (class "Default")
      (node (ref "JP2") (pin "3") (pinfunction "3_3") (pintype "passive"))
      (node (ref "U1") (pin "7") (pinfunction "A6_7") (pintype "bidirectional"))
    )
    (net (code "126") (name "SCK") (class "Default")
      (node (ref "U$2") (pin "28") (pinfunction "(SCK)PB7_28") (pintype "bidirectional"))
      (node (ref "U1") (pin "15") (pinfunction "B5_15") (pintype "bidirectional"))
    )
    (net (code "127") (name "SCK_3V") (class "Default")
      (node (ref "JP1") (pin "1") (pinfunction "1_1") (pintype "passive"))
      (node (ref "U1") (pin "6") (pinfunction "A5_6") (pintype "bidirectional"))
    )
    (net (code "128") (name "SERVO_PWM") (class "Default")
      (node (ref "JP3") (pin "1") (pinfunction "1_1") (pintype "passive"))
      (node (ref "U$2") (pin "3") (pinfunction "PC1_3") (pintype "bidirectional"))
    )
    (net (code "129") (name "STBY") (class "Default")
      (node (ref "C12") (pin "1") (pinfunction "1_1") (pintype "passive"))
      (node (ref "D16") (pin "A") (pinfunction "A_A") (pintype "passive"))
      (node (ref "D17") (pin "A") (pinfunction "A_A") (pintype "passive"))
      (node (ref "R48") (pin "1") (pinfunction "1_1") (pintype "passive"))
      (node (ref "U$2") (pin "17") (pinfunction "PC4_17") (pintype "bidirectional"))
      (node (ref "U$3") (pin "5") (pinfunction "STBY_5") (pintype "bidirectional"))
    )
    (net (code "130") (name "TASTER") (class "Default")
      (node (ref "C33") (pin "1") (pinfunction "1_1") (pintype "passive"))
      (node (ref "IC2") (pin "14") (pinfunction "S3_14") (pintype "input"))
      (node (ref "R22") (pin "2") (pinfunction "2_2") (pintype "passive"))
      (node (ref "S1") (pin "3") (pinfunction "P_3") (pintype "passive"))
      (node (ref "S1") (pin "4") (pinfunction "P1_4") (pintype "passive"))
    )
    (net (code "131") (name "WOL_ETH") (class "Default")
      (node (ref "U1") (pin "18") (pinfunction "B2_18") (pintype "bidirectional"))
    )
    (net (code "132") (name "WOL_ETH_3V") (class "Default")
      (node (ref "JP1") (pin "4") (pinfunction "4_4") (pintype "passive"))
      (node (ref "U1") (pin "3") (pinfunction "A2_3") (pintype "bidirectional"))
    )
    (net (code "133") (name "unconnected-(H1-MOUNT-PadB3,0)") (class "Default")
      (node (ref "H1") (pin "B3,0") (pinfunction "MOUNT_B3,0") (pintype "passive"))
    )
    (net (code "134") (name "unconnected-(H2-MOUNT-PadB3,0)") (class "Default")
      (node (ref "H2") (pin "B3,0") (pinfunction "MOUNT_B3,0") (pintype "passive"))
    )
    (net (code "135") (name "unconnected-(H3-MOUNT-PadB3,0)") (class "Default")
      (node (ref "H3") (pin "B3,0") (pinfunction "MOUNT_B3,0") (pintype "passive"))
    )
    (net (code "136") (name "unconnected-(H4-MOUNT-PadB3,0)") (class "Default")
      (node (ref "H4") (pin "B3,0") (pinfunction "MOUNT_B3,0") (pintype "passive"))
    )
    (net (code "137") (name "unconnected-(IC2A-EN-Pad5)") (class "Default")
      (node (ref "IC2") (pin "5") (pinfunction "EN_5") (pintype "input"))
    )
    (net (code "138") (name "unconnected-(IC2A-Q0-Pad2)") (class "Default")
      (node (ref "IC2") (pin "2") (pinfunction "Q0_2") (pintype "output"))
    )
    (net (code "139") (name "unconnected-(IC2A-Q1-Pad9)") (class "Default")
      (node (ref "IC2") (pin "9") (pinfunction "Q1_9") (pintype "output"))
    )
    (net (code "140") (name "unconnected-(L7-2-Pad8)") (class "Default")
      (node (ref "L7") (pin "8") (pinfunction "2_8") (pintype "passive"))
    )
    (net (code "141") (name "unconnected-(L7-3-Pad10)") (class "Default")
      (node (ref "L7") (pin "10") (pinfunction "3_10") (pintype "passive"))
    )
    (net (code "142") (name "unconnected-(L7-7-Pad5)") (class "Default")
      (node (ref "L7") (pin "5") (pinfunction "7_5") (pintype "passive"))
    )
    (net (code "143") (name "unconnected-(L7-Pad6)") (class "Default")
      (node (ref "L7") (pin "6") (pinfunction "6_6") (pintype "passive"))
    )
    (net (code "144") (name "unconnected-(OK2B-A-Pad3)") (class "Default")
      (node (ref "OK2") (pin "3") (pinfunction "A_3") (pintype "passive"))
    )
    (net (code "145") (name "unconnected-(OK2B-C-Pad4)") (class "Default")
      (node (ref "OK2") (pin "4") (pinfunction "C_4") (pintype "passive"))
    )
    (net (code "146") (name "unconnected-(OK2B-COL-Pad6)") (class "Default")
      (node (ref "OK2") (pin "6") (pinfunction "COL_6") (pintype "passive"))
    )
    (net (code "147") (name "unconnected-(OK2B-EMIT-Pad5)") (class "Default")
      (node (ref "OK2") (pin "5") (pinfunction "EMIT_5") (pintype "passive"))
    )
    (net (code "148") (name "unconnected-(RJ_1-PadP$1)") (class "Default")
      (node (ref "RJ_1") (pin "P$1") (pinfunction "P$1_P$1") (pintype "bidirectional"))
    )
    (net (code "149") (name "unconnected-(RJ_2-PadP$1)") (class "Default")
      (node (ref "RJ_2") (pin "P$1") (pinfunction "P$1_P$1") (pintype "bidirectional"))
    )
    (net (code "150") (name "unconnected-(RJ_2-PadP$4)") (class "Default")
      (node (ref "RJ_2") (pin "P$4") (pinfunction "P$4_P$4") (pintype "bidirectional"))
    )
    (net (code "151") (name "unconnected-(SV1-Pad3)") (class "Default")
      (node (ref "SV1") (pin "3") (pinfunction "3_3") (pintype "passive"))
    )
    (net (code "152") (name "unconnected-(U$1-VREF-Pad5)") (class "Default")
      (node (ref "U$1") (pin "5") (pinfunction "VREF_5") (pintype "output"))
    )
    (net (code "153") (name "unconnected-(U$3-NC-Pad13)") (class "Default")
      (node (ref "U$3") (pin "13") (pinfunction "NC_13") (pintype "bidirectional"))
    )
    (net (code "154") (name "unconnected-(U$3-PFC_STOP-Pad9)") (class "Default")
      (node (ref "U$3") (pin "9") (pinfunction "PFC_STOP_9") (pintype "bidirectional"))
    )
    (net (code "155") (name "unconnected-(U3-NC-Pad3)") (class "Default")
      (node (ref "U3") (pin "3") (pinfunction "NC_3") (pintype "no_connect"))
    )
    (net (code "156") (name "unconnected-(U3-NC_2-Pad2)") (class "Default")
      (node (ref "U3") (pin "2") (pinfunction "NC_2_2") (pintype "no_connect"))
    )
    (net (code "157") (name "unconnected-(U3-ON{slash}~{OFF}-Pad5)") (class "Default")
      (node (ref "U3") (pin "5") (pinfunction "ON/~{OFF}_5") (pintype "input"))
    )
    (net (code "158") (name "unconnected-(U4-NC-Pad3)") (class "Default")
      (node (ref "U4") (pin "3") (pinfunction "NC_3") (pintype "no_connect"))
    )
    (net (code "159") (name "unconnected-(U4-NC_2-Pad2)") (class "Default")
      (node (ref "U4") (pin "2") (pinfunction "NC_2_2") (pintype "no_connect"))
    )
    (net (code "160") (name "unconnected-(U4-ON{slash}~{OFF}-Pad5)") (class "Default")
      (node (ref "U4") (pin "5") (pinfunction "ON/~{OFF}_5") (pintype "input"))
    )
    (net (code "161") (name "unconnected-(U5-OUTC-Pad10)") (class "Default")
      (node (ref "U5") (pin "10") (pinfunction "OUTC_10") (pintype "output"))
    )
    (net (code "162") (name "ÜBERSPANNUNG") (class "Default")
      (node (ref "C24") (pin "1") (pinfunction "1_1") (pintype "passive"))
      (node (ref "IC2") (pin "12") (pinfunction "S2_12") (pintype "input"))
      (node (ref "OK2") (pin "7") (pinfunction "EMIT_7") (pintype "passive"))
      (node (ref "R10") (pin "2") (pinfunction "2_2") (pintype "passive"))
    )
  )
)
